# InteractionBoard_temp.net
KiCad netlist of a schematic drawn in EAGLE
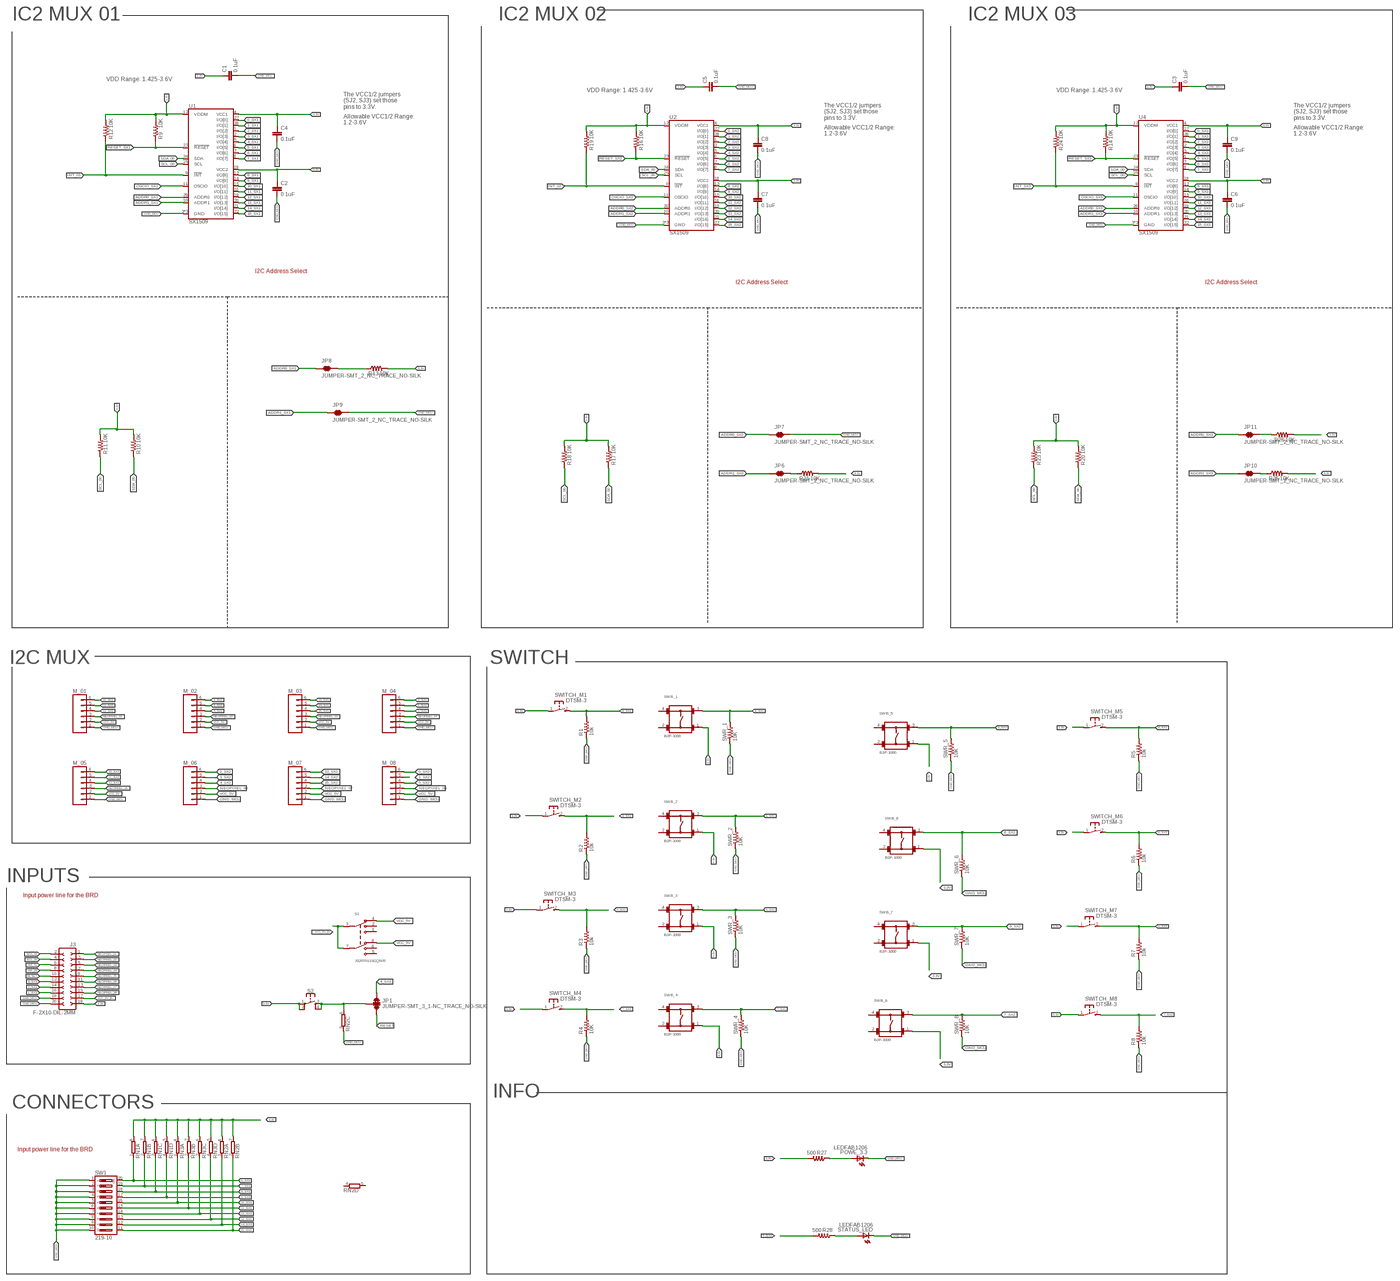
[diagram p0: schematic, sheet 1, overview]
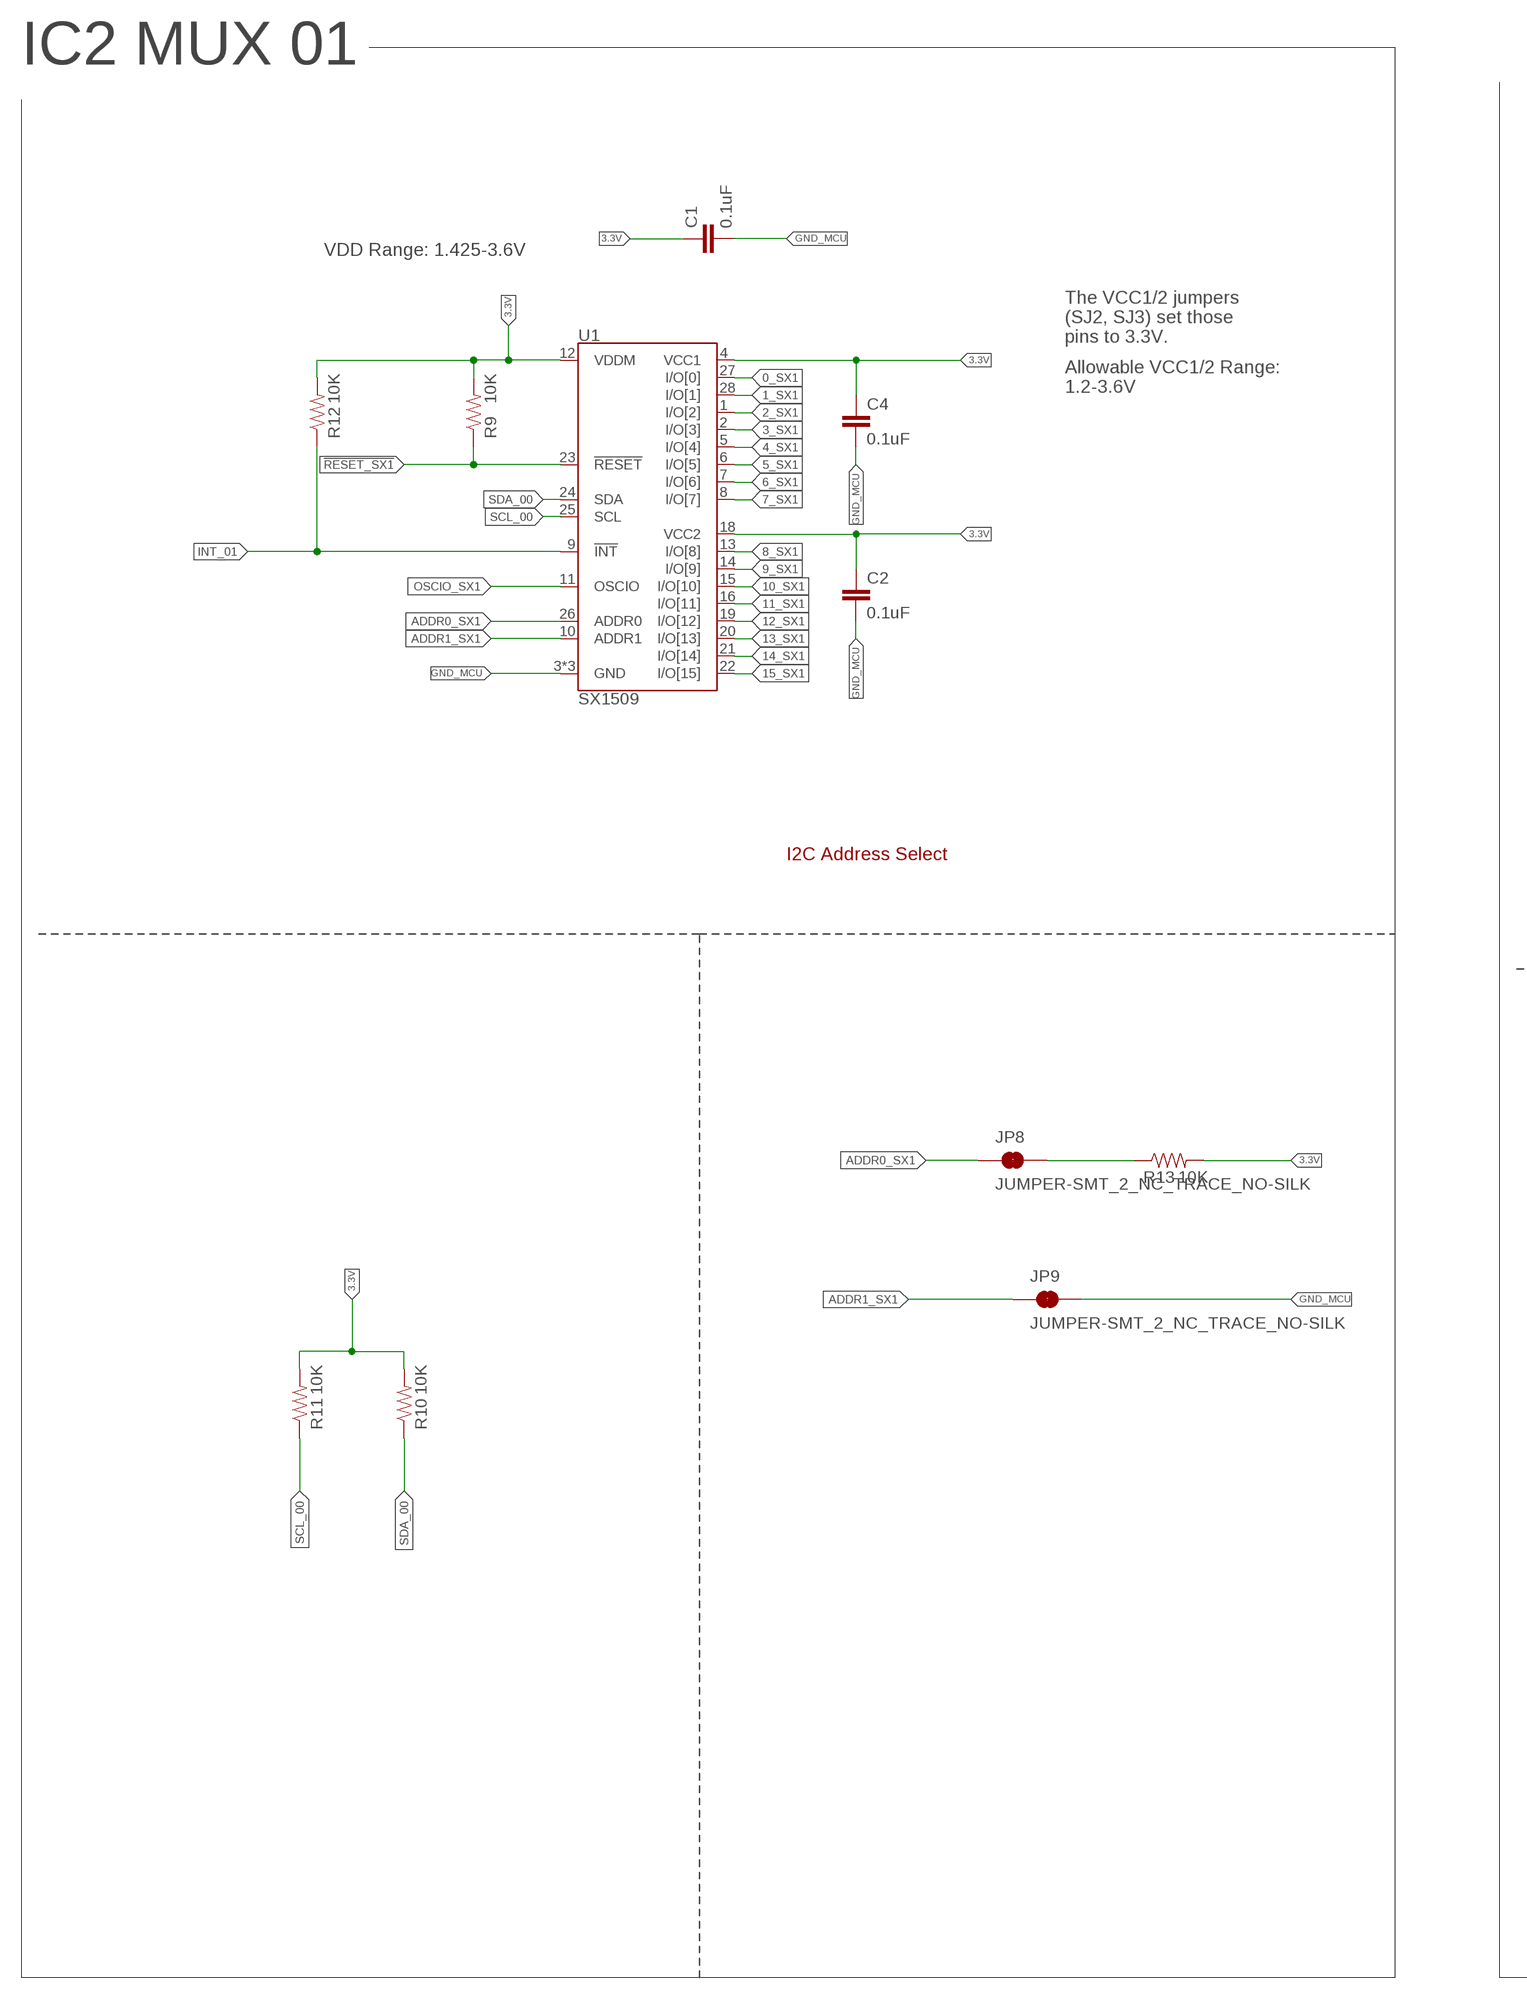
[diagram p1: schematic, sheet 1, part 1 of 4]
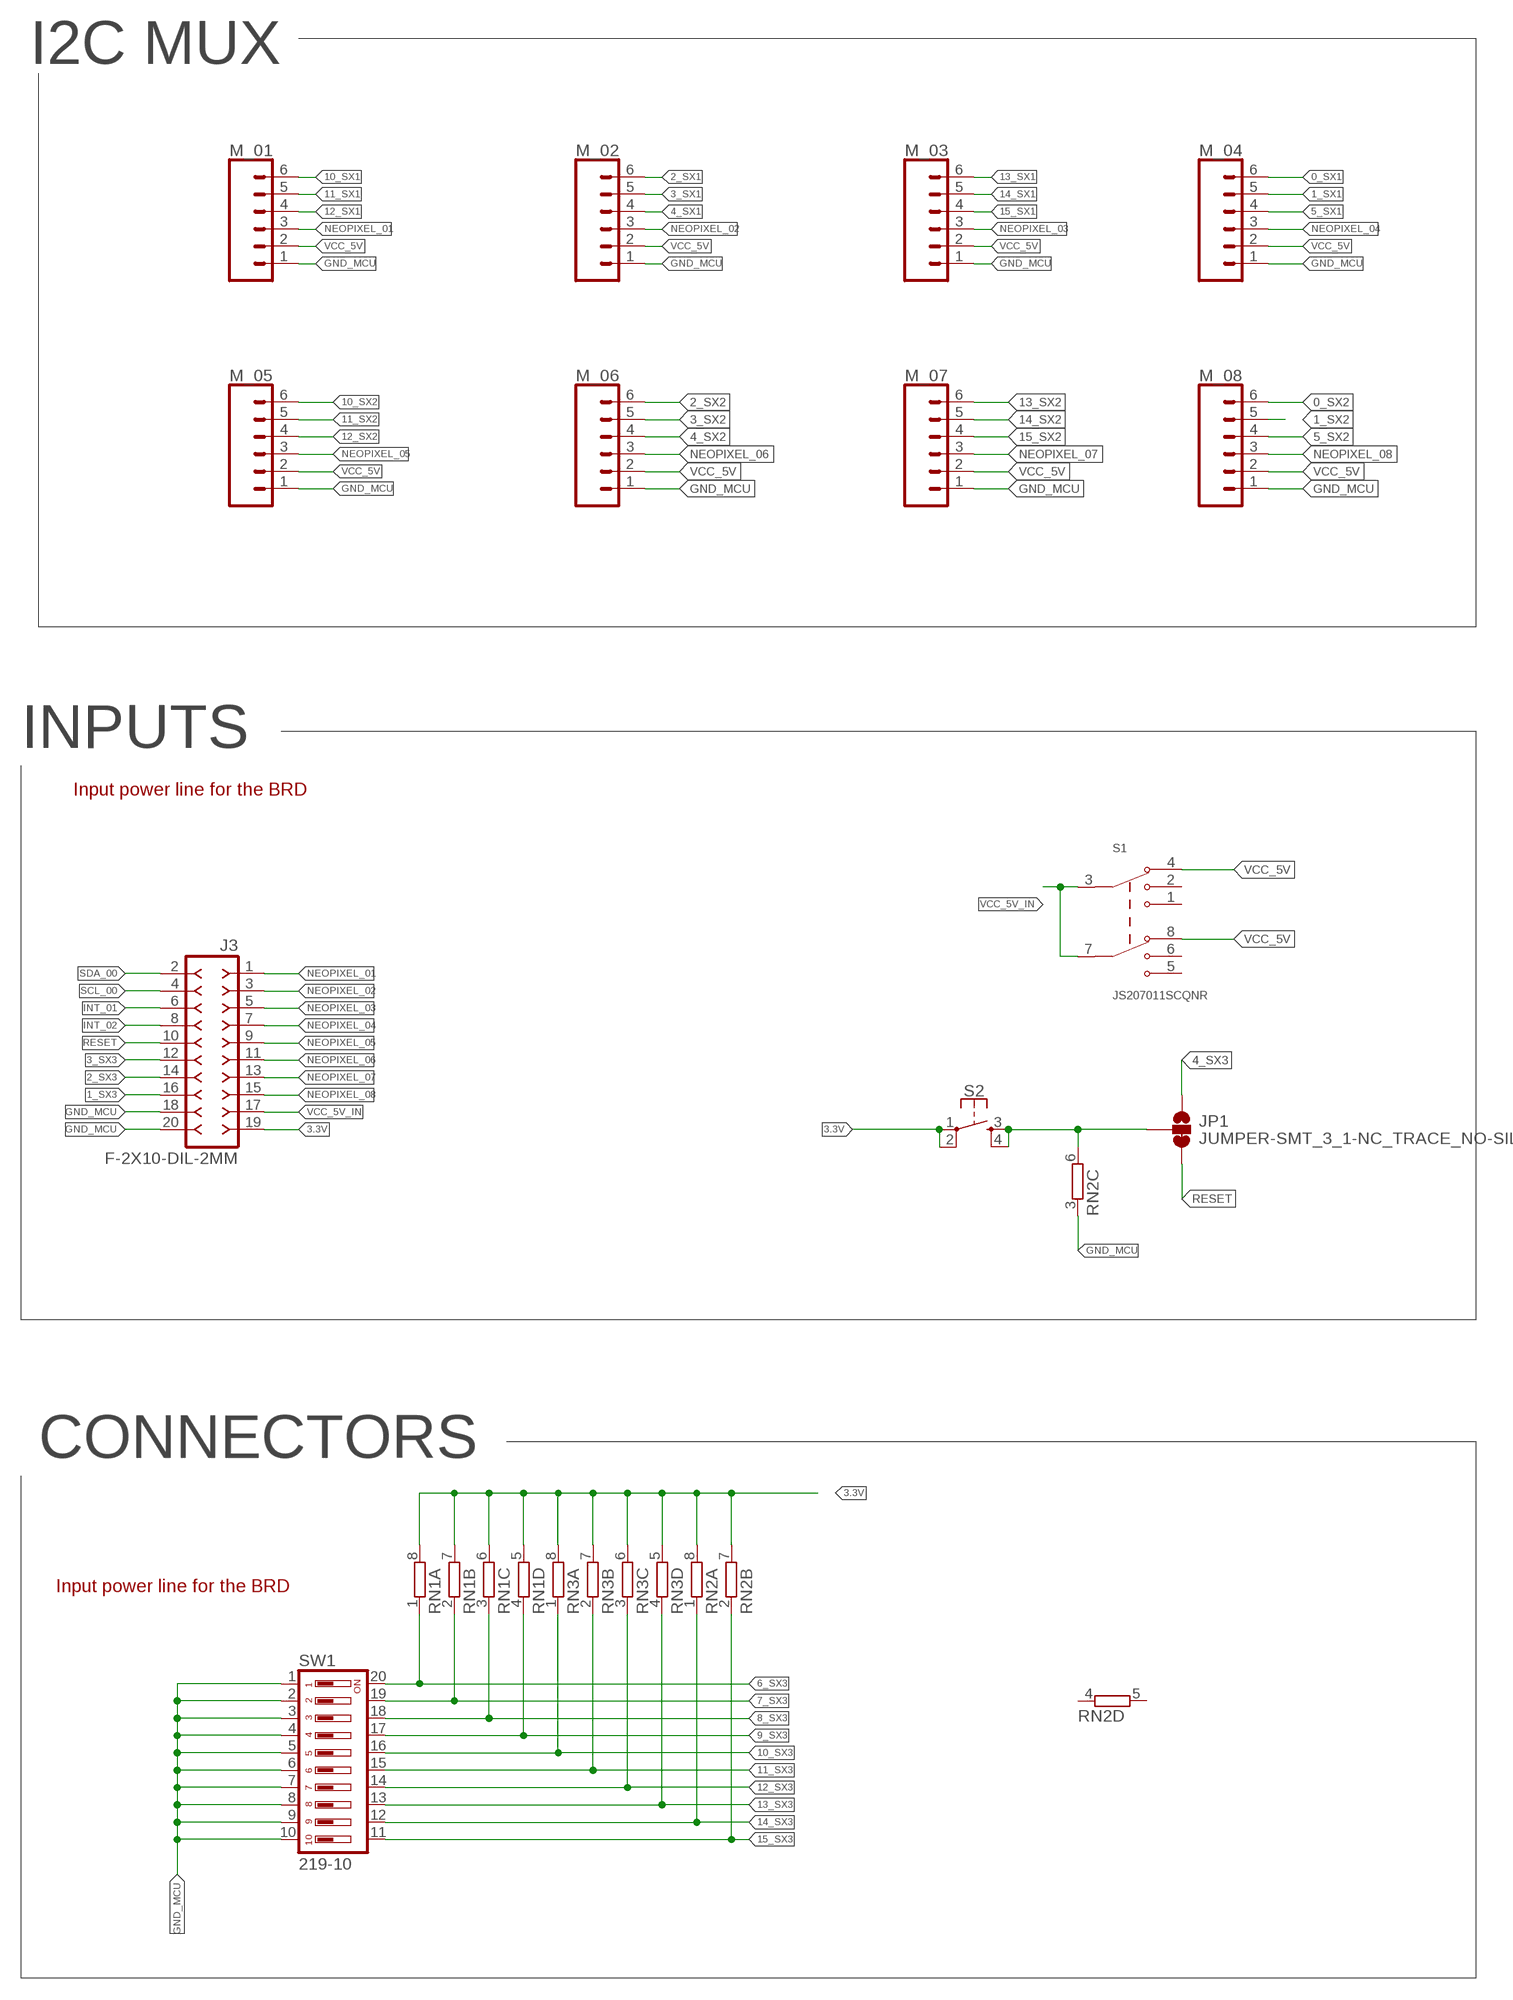
[diagram p2: schematic, sheet 1, part 2 of 4]
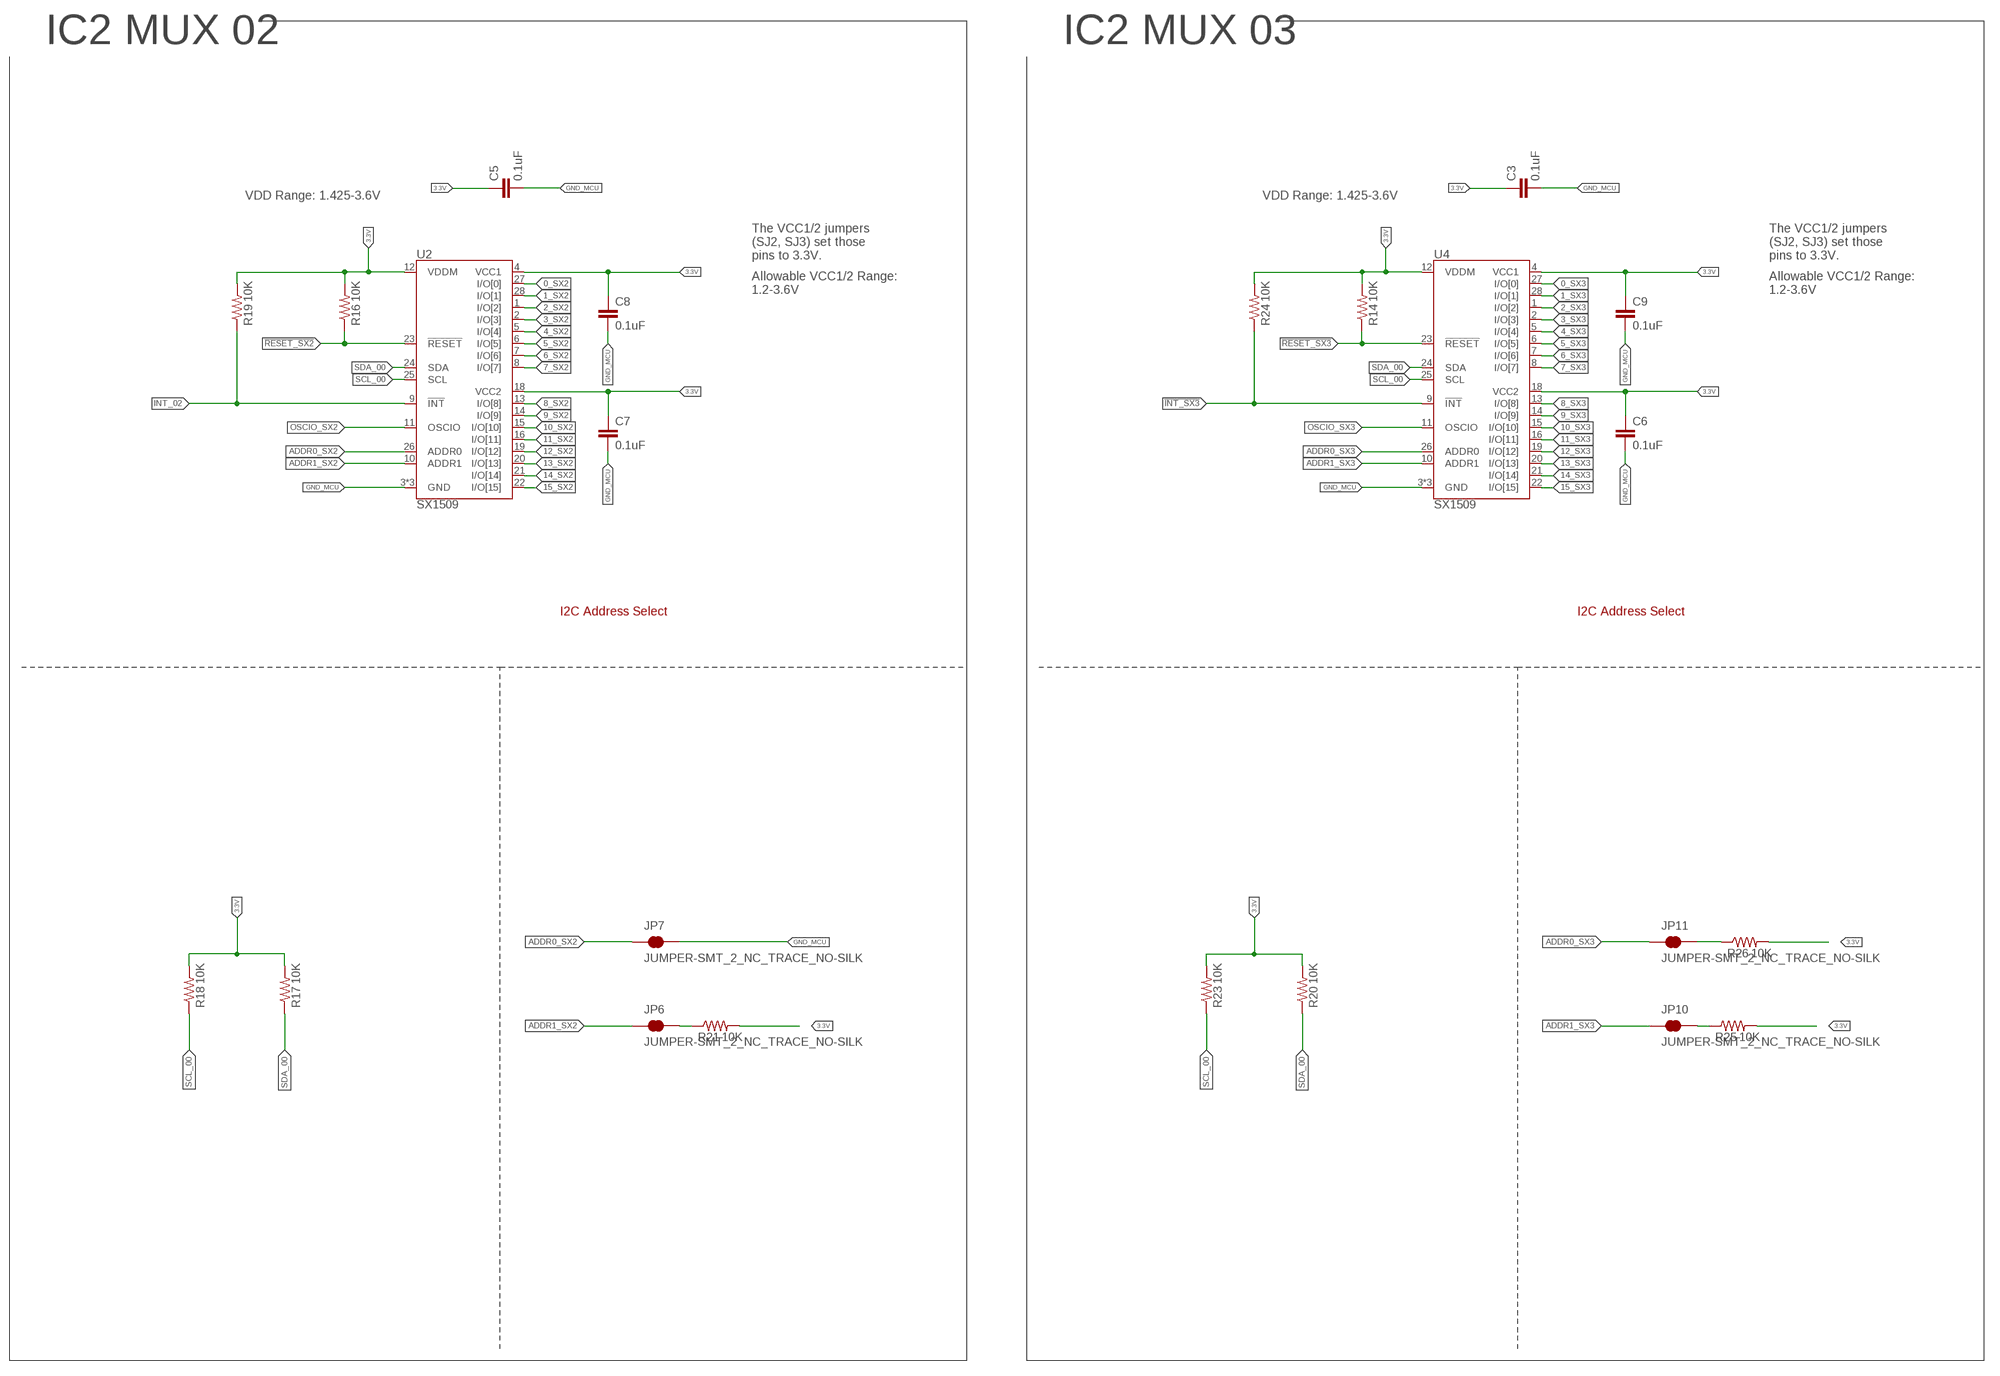
[diagram p3: schematic, sheet 1, part 3 of 4]
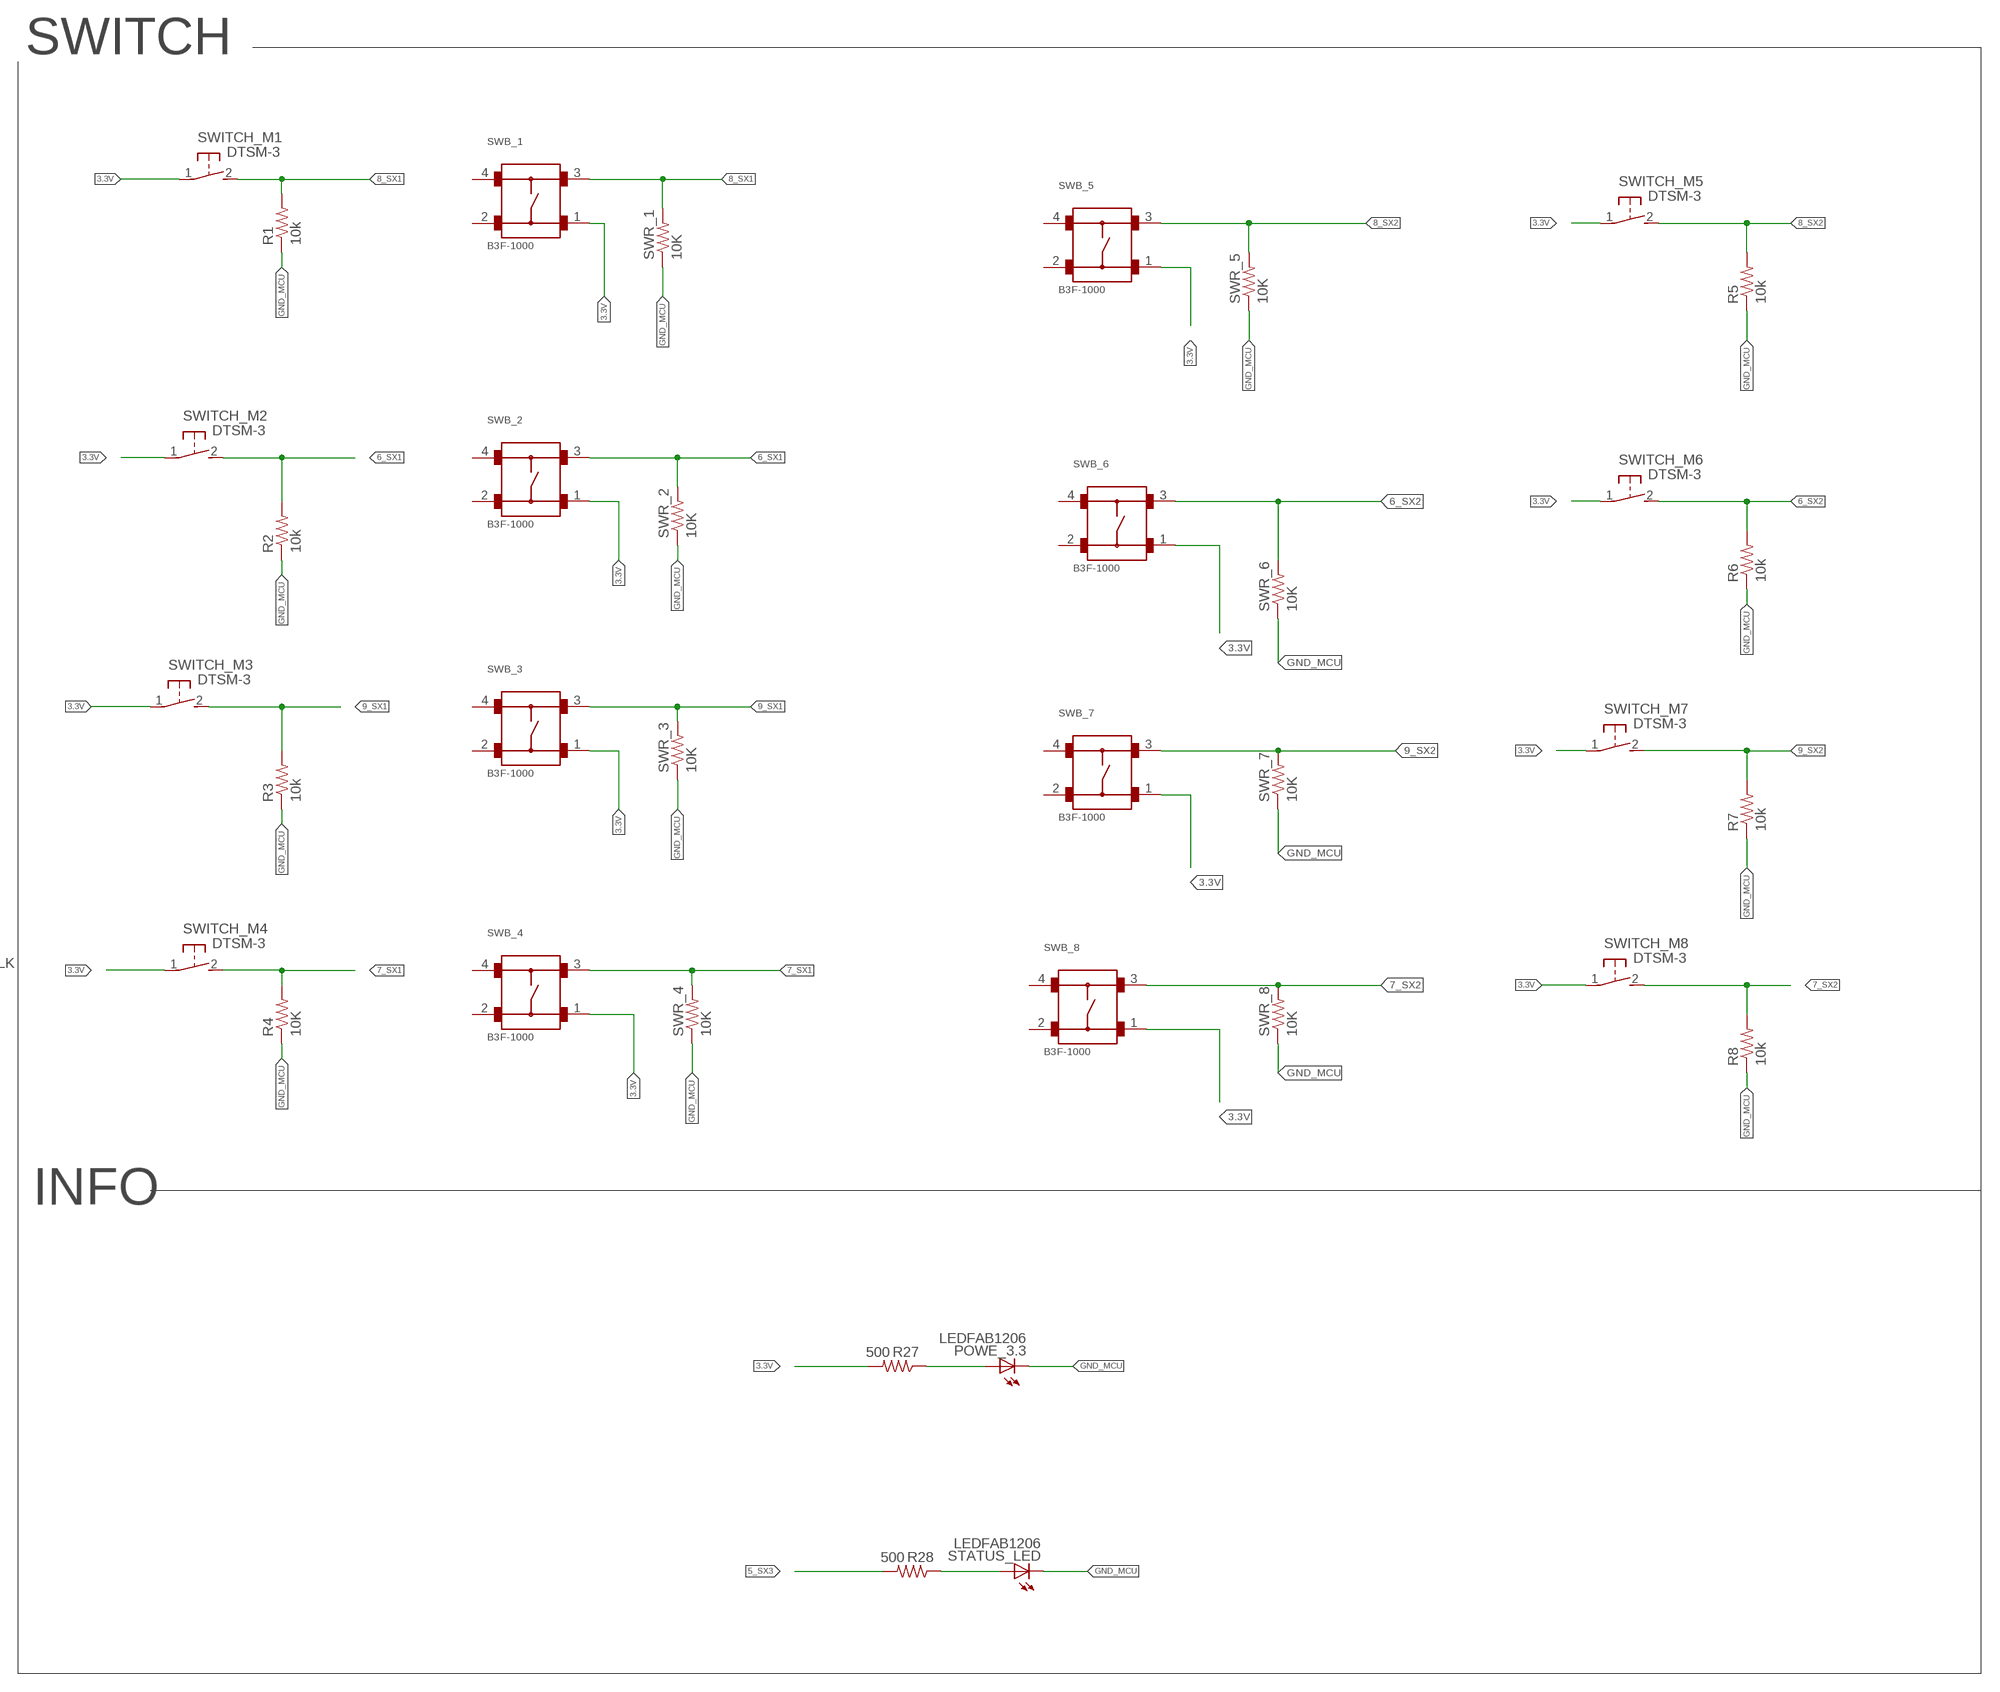
[diagram p4: schematic, sheet 1, part 4 of 4]

(export (version "E")
  (design (tool "Eeschema 10.0.6"))
  (components
    (comp (ref "C1")
      (value "0.1uF")
      (footprint "eagle-import:0603-CAP")
      (libsource (lib "eagle-import") (part "0.1UF-25V(+80/-20%)(0603)"))
    )
    (comp (ref "C2")
      (value "0.1uF")
      (footprint "eagle-import:0603-CAP")
      (libsource (lib "eagle-import") (part "0.1UF-25V(+80/-20%)(0603)"))
    )
    (comp (ref "C3")
      (value "0.1uF")
      (footprint "eagle-import:0603-CAP")
      (libsource (lib "eagle-import") (part "0.1UF-25V(+80/-20%)(0603)"))
    )
    (comp (ref "C4")
      (value "0.1uF")
      (footprint "eagle-import:0603-CAP")
      (libsource (lib "eagle-import") (part "0.1UF-25V(+80/-20%)(0603)"))
    )
    (comp (ref "C5")
      (value "0.1uF")
      (footprint "eagle-import:0603-CAP")
      (libsource (lib "eagle-import") (part "0.1UF-25V(+80/-20%)(0603)"))
    )
    (comp (ref "C6")
      (value "0.1uF")
      (footprint "eagle-import:0603-CAP")
      (libsource (lib "eagle-import") (part "0.1UF-25V(+80/-20%)(0603)"))
    )
    (comp (ref "C7")
      (value "0.1uF")
      (footprint "eagle-import:0603-CAP")
      (libsource (lib "eagle-import") (part "0.1UF-25V(+80/-20%)(0603)"))
    )
    (comp (ref "C8")
      (value "0.1uF")
      (footprint "eagle-import:0603-CAP")
      (libsource (lib "eagle-import") (part "0.1UF-25V(+80/-20%)(0603)"))
    )
    (comp (ref "C9")
      (value "0.1uF")
      (footprint "eagle-import:0603-CAP")
      (libsource (lib "eagle-import") (part "0.1UF-25V(+80/-20%)(0603)"))
    )
    (comp (ref "J3")
      (value "F-2X10-DIL-2MM")
      (footprint "eagle-import:DIL-2MM-2X10")
      (libsource (lib "eagle-import") (part "F-2X10-DIL-2MM"))
    )
    (comp (ref "JP1")
      (value "JUMPER-SMT_3_1-NC_TRACE_NO-SILK")
      (footprint "eagle-import:SMT-JUMPER_3_1-NC_TRACE_NO-SILK")
      (libsource (lib "eagle-import") (part "JUMPER-SMT_3_1-NC_TRACE_NO-SILK"))
    )
    (comp (ref "JP6")
      (value "JUMPER-SMT_2_NC_TRACE_NO-SILK")
      (footprint "eagle-import:SMT-JUMPER_2_NC_TRACE_NO-SILK")
      (libsource (lib "eagle-import") (part "JUMPER-SMT_2_NC_TRACE_NO-SILK"))
    )
    (comp (ref "JP7")
      (value "JUMPER-SMT_2_NC_TRACE_NO-SILK")
      (footprint "eagle-import:SMT-JUMPER_2_NC_TRACE_NO-SILK")
      (libsource (lib "eagle-import") (part "JUMPER-SMT_2_NC_TRACE_NO-SILK"))
    )
    (comp (ref "JP8")
      (value "JUMPER-SMT_2_NC_TRACE_NO-SILK")
      (footprint "eagle-import:SMT-JUMPER_2_NC_TRACE_NO-SILK")
      (libsource (lib "eagle-import") (part "JUMPER-SMT_2_NC_TRACE_NO-SILK"))
    )
    (comp (ref "JP9")
      (value "JUMPER-SMT_2_NC_TRACE_NO-SILK")
      (footprint "eagle-import:SMT-JUMPER_2_NC_TRACE_NO-SILK")
      (libsource (lib "eagle-import") (part "JUMPER-SMT_2_NC_TRACE_NO-SILK"))
    )
    (comp (ref "JP10")
      (value "JUMPER-SMT_2_NC_TRACE_NO-SILK")
      (footprint "eagle-import:SMT-JUMPER_2_NC_TRACE_NO-SILK")
      (libsource (lib "eagle-import") (part "JUMPER-SMT_2_NC_TRACE_NO-SILK"))
    )
    (comp (ref "JP11")
      (value "JUMPER-SMT_2_NC_TRACE_NO-SILK")
      (footprint "eagle-import:SMT-JUMPER_2_NC_TRACE_NO-SILK")
      (libsource (lib "eagle-import") (part "JUMPER-SMT_2_NC_TRACE_NO-SILK"))
    )
    (comp (ref "M_01")
      (value "CONN_06SMD-1MM")
      (footprint "eagle-import:1X06-1MM")
      (libsource (lib "eagle-import") (part "CONN_06SMD-1MM"))
    )
    (comp (ref "M_02")
      (value "CONN_06SMD-1MM")
      (footprint "eagle-import:1X06-1MM")
      (libsource (lib "eagle-import") (part "CONN_06SMD-1MM"))
    )
    (comp (ref "M_03")
      (value "CONN_06SMD-1MM")
      (footprint "eagle-import:1X06-1MM")
      (libsource (lib "eagle-import") (part "CONN_06SMD-1MM"))
    )
    (comp (ref "M_04")
      (value "CONN_06SMD-1MM")
      (footprint "eagle-import:1X06-1MM")
      (libsource (lib "eagle-import") (part "CONN_06SMD-1MM"))
    )
    (comp (ref "M_05")
      (value "CONN_06SMD-1MM")
      (footprint "eagle-import:1X06-1MM")
      (libsource (lib "eagle-import") (part "CONN_06SMD-1MM"))
    )
    (comp (ref "M_06")
      (value "CONN_06SMD-1MM")
      (footprint "eagle-import:1X06-1MM")
      (libsource (lib "eagle-import") (part "CONN_06SMD-1MM"))
    )
    (comp (ref "M_07")
      (value "CONN_06SMD-1MM")
      (footprint "eagle-import:1X06-1MM")
      (libsource (lib "eagle-import") (part "CONN_06SMD-1MM"))
    )
    (comp (ref "M_08")
      (value "CONN_06SMD-1MM")
      (footprint "eagle-import:1X06-1MM")
      (libsource (lib "eagle-import") (part "CONN_06SMD-1MM"))
    )
    (comp (ref "POWE_3.3")
      (value "LEDFAB1206")
      (footprint "eagle-import:LED1206FAB")
      (libsource (lib "eagle-import") (part "LEDFAB1206"))
    )
    (comp (ref "R1")
      (value "10k")
      (footprint "eagle-import:M0805")
      (libsource (lib "eagle-import") (part "R-US_M0805"))
    )
    (comp (ref "R2")
      (value "10k")
      (footprint "eagle-import:M0805")
      (libsource (lib "eagle-import") (part "R-US_M0805"))
    )
    (comp (ref "R3")
      (value "10k")
      (footprint "eagle-import:M0805")
      (libsource (lib "eagle-import") (part "R-US_M0805"))
    )
    (comp (ref "R4")
      (value "10K")
      (footprint "eagle-import:M0805")
      (libsource (lib "eagle-import") (part "R-US_M0805"))
    )
    (comp (ref "R5")
      (value "10k")
      (footprint "eagle-import:M0805")
      (libsource (lib "eagle-import") (part "R-US_M0805"))
    )
    (comp (ref "R6")
      (value "10k")
      (footprint "eagle-import:M0805")
      (libsource (lib "eagle-import") (part "R-US_M0805"))
    )
    (comp (ref "R7")
      (value "10k")
      (footprint "eagle-import:M0805")
      (libsource (lib "eagle-import") (part "R-US_M0805"))
    )
    (comp (ref "R8")
      (value "10k")
      (footprint "eagle-import:M0805")
      (libsource (lib "eagle-import") (part "R-US_M0805"))
    )
    (comp (ref "R9")
      (value "10K")
      (footprint "eagle-import:0603-RES")
      (libsource (lib "eagle-import") (part "SparkFun-Resistors_532_10KOHM-1/10W-1%(0603)0603"))
    )
    (comp (ref "R10")
      (value "10K")
      (footprint "eagle-import:0603-RES")
      (libsource (lib "eagle-import") (part "SparkFun-Resistors_532_10KOHM-1/10W-1%(0603)0603"))
    )
    (comp (ref "R11")
      (value "10K")
      (footprint "eagle-import:0603-RES")
      (libsource (lib "eagle-import") (part "SparkFun-Resistors_532_10KOHM-1/10W-1%(0603)0603"))
    )
    (comp (ref "R12")
      (value "10K")
      (footprint "eagle-import:0603-RES")
      (libsource (lib "eagle-import") (part "SparkFun-Resistors_532_10KOHM-1/10W-1%(0603)0603"))
    )
    (comp (ref "R13")
      (value "10K")
      (footprint "eagle-import:0603-RES")
      (libsource (lib "eagle-import") (part "SparkFun-Resistors_532_10KOHM-1/10W-1%(0603)0603"))
    )
    (comp (ref "R14")
      (value "10K")
      (footprint "eagle-import:0603-RES")
      (libsource (lib "eagle-import") (part "SparkFun-Resistors_532_10KOHM-1/10W-1%(0603)0603"))
    )
    (comp (ref "R16")
      (value "10K")
      (footprint "eagle-import:0603-RES")
      (libsource (lib "eagle-import") (part "SparkFun-Resistors_532_10KOHM-1/10W-1%(0603)0603"))
    )
    (comp (ref "R17")
      (value "10K")
      (footprint "eagle-import:0603-RES")
      (libsource (lib "eagle-import") (part "SparkFun-Resistors_532_10KOHM-1/10W-1%(0603)0603"))
    )
    (comp (ref "R18")
      (value "10K")
      (footprint "eagle-import:0603-RES")
      (libsource (lib "eagle-import") (part "SparkFun-Resistors_532_10KOHM-1/10W-1%(0603)0603"))
    )
    (comp (ref "R19")
      (value "10K")
      (footprint "eagle-import:0603-RES")
      (libsource (lib "eagle-import") (part "SparkFun-Resistors_532_10KOHM-1/10W-1%(0603)0603"))
    )
    (comp (ref "R20")
      (value "10K")
      (footprint "eagle-import:0603-RES")
      (libsource (lib "eagle-import") (part "SparkFun-Resistors_532_10KOHM-1/10W-1%(0603)0603"))
    )
    (comp (ref "R21")
      (value "10K")
      (footprint "eagle-import:0603-RES")
      (libsource (lib "eagle-import") (part "SparkFun-Resistors_532_10KOHM-1/10W-1%(0603)0603"))
    )
    (comp (ref "R23")
      (value "10K")
      (footprint "eagle-import:0603-RES")
      (libsource (lib "eagle-import") (part "SparkFun-Resistors_532_10KOHM-1/10W-1%(0603)0603"))
    )
    (comp (ref "R24")
      (value "10K")
      (footprint "eagle-import:0603-RES")
      (libsource (lib "eagle-import") (part "SparkFun-Resistors_532_10KOHM-1/10W-1%(0603)0603"))
    )
    (comp (ref "R25")
      (value "10K")
      (footprint "eagle-import:0603-RES")
      (libsource (lib "eagle-import") (part "SparkFun-Resistors_532_10KOHM-1/10W-1%(0603)0603"))
    )
    (comp (ref "R26")
      (value "10K")
      (footprint "eagle-import:0603-RES")
      (libsource (lib "eagle-import") (part "SparkFun-Resistors_532_10KOHM-1/10W-1%(0603)0603"))
    )
    (comp (ref "R27")
      (value "500")
      (footprint "eagle-import:0603-RES")
      (libsource (lib "eagle-import") (part "10KOHM-1/10W-1%(0603)0603"))
    )
    (comp (ref "R28")
      (value "500")
      (footprint "eagle-import:0603-RES")
      (libsource (lib "eagle-import") (part "10KOHM-1/10W-1%(0603)0603"))
    )
    (comp (ref "RN1")
      (value "4R-NEXB38V")
      (footprint "eagle-import:EXB38V")
      (libsource (lib "eagle-import") (part "4R-NEXB38V"))
    )
    (comp (ref "RN2")
      (value "4R-NEXB38V")
      (footprint "eagle-import:EXB38V")
      (libsource (lib "eagle-import") (part "4R-NEXB38V"))
    )
    (comp (ref "RN3")
      (value "4R-NEXB38V")
      (footprint "eagle-import:EXB38V")
      (libsource (lib "eagle-import") (part "4R-NEXB38V"))
    )
    (comp (ref "S1")
      (value "JS207011SCQNR")
      (footprint "eagle-import:SW_JS207011SCQNR")
      (fields (field (name "MF") "C&K"))
      (libsource (lib "eagle-import") (part "JS207011SCQNR"))
    )
    (comp (ref "S2")
      (value "MOMENTARY-SWITCH-SPST-2-SMD-5.2MM")
      (footprint "eagle-import:TACTILE_SWITCH_SMD_5.2MM")
      (libsource (lib "eagle-import") (part "MOMENTARY-SWITCH-SPST-2-SMD-5.2MM"))
    )
    (comp (ref "STATUS_LED")
      (value "LEDFAB1206")
      (footprint "eagle-import:LED1206FAB")
      (libsource (lib "eagle-import") (part "LEDFAB1206"))
    )
    (comp (ref "SW1")
      (value "219-10")
      (footprint "eagle-import:CTS-219-10")
      (fields (field (name "MF") "SLI (CML/IDI)") (field (name "MPN") "219-10PK"))
      (libsource (lib "eagle-import") (part "219-10"))
    )
    (comp (ref "SWB_1")
      (value "B3F-1000")
      (footprint "eagle-import:B3F-1000")
      (fields
        (field (name "DIGI_KEY_PART_NUMBER") "SW400-ND")
        (field (name "MANUFACTURER") "Omron Electronics Inc-EMC Div")
        (field (name "CREATED_BY") "PCBLayout.com")
      )
      (libsource (lib "eagle-import") (part "B3F-1000"))
    )
    (comp (ref "SWB_2")
      (value "B3F-1000")
      (footprint "eagle-import:B3F-1000")
      (fields
        (field (name "DIGI_KEY_PART_NUMBER") "SW400-ND")
        (field (name "MANUFACTURER") "Omron Electronics Inc-EMC Div")
        (field (name "CREATED_BY") "PCBLayout.com")
      )
      (libsource (lib "eagle-import") (part "B3F-1000"))
    )
    (comp (ref "SWB_3")
      (value "B3F-1000")
      (footprint "eagle-import:B3F-1000")
      (fields
        (field (name "DIGI_KEY_PART_NUMBER") "SW400-ND")
        (field (name "MANUFACTURER") "Omron Electronics Inc-EMC Div")
        (field (name "CREATED_BY") "PCBLayout.com")
      )
      (libsource (lib "eagle-import") (part "B3F-1000"))
    )
    (comp (ref "SWB_4")
      (value "B3F-1000")
      (footprint "eagle-import:B3F-1000")
      (fields
        (field (name "DIGI_KEY_PART_NUMBER") "SW400-ND")
        (field (name "MANUFACTURER") "Omron Electronics Inc-EMC Div")
        (field (name "CREATED_BY") "PCBLayout.com")
      )
      (libsource (lib "eagle-import") (part "B3F-1000"))
    )
    (comp (ref "SWB_5")
      (value "B3F-1000")
      (footprint "eagle-import:B3F-1000")
      (fields
        (field (name "DIGI_KEY_PART_NUMBER") "SW400-ND")
        (field (name "MANUFACTURER") "Omron Electronics Inc-EMC Div")
        (field (name "CREATED_BY") "PCBLayout.com")
      )
      (libsource (lib "eagle-import") (part "B3F-1000"))
    )
    (comp (ref "SWB_6")
      (value "B3F-1000")
      (footprint "eagle-import:B3F-1000")
      (fields
        (field (name "DIGI_KEY_PART_NUMBER") "SW400-ND")
        (field (name "MANUFACTURER") "Omron Electronics Inc-EMC Div")
        (field (name "CREATED_BY") "PCBLayout.com")
      )
      (libsource (lib "eagle-import") (part "B3F-1000"))
    )
    (comp (ref "SWB_7")
      (value "B3F-1000")
      (footprint "eagle-import:B3F-1000")
      (fields
        (field (name "DIGI_KEY_PART_NUMBER") "SW400-ND")
        (field (name "MANUFACTURER") "Omron Electronics Inc-EMC Div")
        (field (name "CREATED_BY") "PCBLayout.com")
      )
      (libsource (lib "eagle-import") (part "B3F-1000"))
    )
    (comp (ref "SWB_8")
      (value "B3F-1000")
      (footprint "eagle-import:B3F-1000")
      (fields
        (field (name "DIGI_KEY_PART_NUMBER") "SW400-ND")
        (field (name "MANUFACTURER") "Omron Electronics Inc-EMC Div")
        (field (name "CREATED_BY") "PCBLayout.com")
      )
      (libsource (lib "eagle-import") (part "B3F-1000"))
    )
    (comp (ref "SWITCH_M1")
      (value "DTSM-3")
      (footprint "eagle-import:DTSM-3")
      (libsource (lib "eagle-import") (part "DTSM-3"))
    )
    (comp (ref "SWITCH_M2")
      (value "DTSM-3")
      (footprint "eagle-import:DTSM-3")
      (libsource (lib "eagle-import") (part "DTSM-3"))
    )
    (comp (ref "SWITCH_M3")
      (value "DTSM-3")
      (footprint "eagle-import:DTSM-3")
      (libsource (lib "eagle-import") (part "DTSM-3"))
    )
    (comp (ref "SWITCH_M4")
      (value "DTSM-3")
      (footprint "eagle-import:DTSM-3")
      (libsource (lib "eagle-import") (part "DTSM-3"))
    )
    (comp (ref "SWITCH_M5")
      (value "DTSM-3")
      (footprint "eagle-import:DTSM-3")
      (libsource (lib "eagle-import") (part "DTSM-3"))
    )
    (comp (ref "SWITCH_M6")
      (value "DTSM-3")
      (footprint "eagle-import:DTSM-3")
      (libsource (lib "eagle-import") (part "DTSM-3"))
    )
    (comp (ref "SWITCH_M7")
      (value "DTSM-3")
      (footprint "eagle-import:DTSM-3")
      (libsource (lib "eagle-import") (part "DTSM-3"))
    )
    (comp (ref "SWITCH_M8")
      (value "DTSM-3")
      (footprint "eagle-import:DTSM-3")
      (libsource (lib "eagle-import") (part "DTSM-3"))
    )
    (comp (ref "SWR_1")
      (value "10K")
      (footprint "eagle-import:M0805")
      (libsource (lib "eagle-import") (part "R-US_M0805"))
    )
    (comp (ref "SWR_2")
      (value "10K")
      (footprint "eagle-import:M0805")
      (libsource (lib "eagle-import") (part "R-US_M0805"))
    )
    (comp (ref "SWR_3")
      (value "10K")
      (footprint "eagle-import:M0805")
      (libsource (lib "eagle-import") (part "R-US_M0805"))
    )
    (comp (ref "SWR_4")
      (value "10K")
      (footprint "eagle-import:M0805")
      (libsource (lib "eagle-import") (part "R-US_M0805"))
    )
    (comp (ref "SWR_5")
      (value "10K")
      (footprint "eagle-import:M0805")
      (libsource (lib "eagle-import") (part "R-US_M0805"))
    )
    (comp (ref "SWR_6")
      (value "10K")
      (footprint "eagle-import:M0805")
      (libsource (lib "eagle-import") (part "R-US_M0805"))
    )
    (comp (ref "SWR_7")
      (value "10K")
      (footprint "eagle-import:M0805")
      (libsource (lib "eagle-import") (part "R-US_M0805"))
    )
    (comp (ref "SWR_8")
      (value "10K")
      (footprint "eagle-import:M0805")
      (libsource (lib "eagle-import") (part "R-US_M0805"))
    )
    (comp (ref "U1")
      (value "SX1509")
      (footprint "eagle-import:QFN-28")
      (libsource (lib "eagle-import") (part "SX1509"))
    )
    (comp (ref "U2")
      (value "SX1509")
      (footprint "eagle-import:QFN-28")
      (libsource (lib "eagle-import") (part "SX1509"))
    )
    (comp (ref "U4")
      (value "SX1509")
      (footprint "eagle-import:QFN-28")
      (libsource (lib "eagle-import") (part "SX1509"))
    )
  )
  (nets
    (net (code "1") (name "/~{INT_SX3}") (class "Default")
      (node (ref "R24") (pin "1") (pinfunction "1_1") (pintype "passive"))
      (node (ref "U4") (pin "9") (pinfunction "~{INT}_9") (pintype "bidirectional"))
    )
    (net (code "2") (name "/~{RESET_SX1}") (class "Default")
      (node (ref "R9") (pin "1") (pinfunction "1_1") (pintype "passive"))
      (node (ref "U1") (pin "23") (pinfunction "~{RESET}_23") (pintype "bidirectional"))
    )
    (net (code "3") (name "/~{RESET_SX2}") (class "Default")
      (node (ref "R16") (pin "1") (pinfunction "1_1") (pintype "passive"))
      (node (ref "U2") (pin "23") (pinfunction "~{RESET}_23") (pintype "bidirectional"))
    )
    (net (code "4") (name "/~{RESET_SX3}") (class "Default")
      (node (ref "R14") (pin "1") (pinfunction "1_1") (pintype "passive"))
      (node (ref "U4") (pin "23") (pinfunction "~{RESET}_23") (pintype "bidirectional"))
    )
    (net (code "5") (name "0_SX1") (class "Default")
      (node (ref "M_04") (pin "6") (pinfunction "6_6") (pintype "passive"))
      (node (ref "U1") (pin "27") (pinfunction "I/O[0]_27") (pintype "bidirectional"))
    )
    (net (code "6") (name "0_SX2") (class "Default")
      (node (ref "M_08") (pin "6") (pinfunction "6_6") (pintype "passive"))
      (node (ref "U2") (pin "27") (pinfunction "I/O[0]_27") (pintype "bidirectional"))
    )
    (net (code "7") (name "0_SX3") (class "Default")
      (node (ref "U4") (pin "27") (pinfunction "I/O[0]_27") (pintype "bidirectional"))
    )
    (net (code "8") (name "1_SX1") (class "Default")
      (node (ref "M_04") (pin "5") (pinfunction "5_5") (pintype "passive"))
      (node (ref "U1") (pin "28") (pinfunction "I/O[1]_28") (pintype "bidirectional"))
    )
    (net (code "9") (name "1_SX2") (class "Default")
      (node (ref "M_08") (pin "5") (pinfunction "5_5") (pintype "passive"))
      (node (ref "U2") (pin "28") (pinfunction "I/O[1]_28") (pintype "bidirectional"))
    )
    (net (code "10") (name "1_SX3") (class "Default")
      (node (ref "J3") (pin "16") (pinfunction "16_16") (pintype "passive"))
      (node (ref "U4") (pin "28") (pinfunction "I/O[1]_28") (pintype "bidirectional"))
    )
    (net (code "11") (name "2_SX1") (class "Default")
      (node (ref "M_02") (pin "6") (pinfunction "6_6") (pintype "passive"))
      (node (ref "U1") (pin "1") (pinfunction "I/O[2]_1") (pintype "bidirectional"))
    )
    (net (code "12") (name "2_SX2") (class "Default")
      (node (ref "M_06") (pin "6") (pinfunction "6_6") (pintype "passive"))
      (node (ref "U2") (pin "1") (pinfunction "I/O[2]_1") (pintype "bidirectional"))
    )
    (net (code "13") (name "2_SX3") (class "Default")
      (node (ref "J3") (pin "14") (pinfunction "14_14") (pintype "passive"))
      (node (ref "U4") (pin "1") (pinfunction "I/O[2]_1") (pintype "bidirectional"))
    )
    (net (code "14") (name "3.3V") (class "Default")
      (node (ref "C1") (pin "1") (pinfunction "1_1") (pintype "passive"))
      (node (ref "C2") (pin "1") (pinfunction "1_1") (pintype "passive"))
      (node (ref "C3") (pin "1") (pinfunction "1_1") (pintype "passive"))
      (node (ref "C4") (pin "1") (pinfunction "1_1") (pintype "passive"))
      (node (ref "C5") (pin "1") (pinfunction "1_1") (pintype "passive"))
      (node (ref "C6") (pin "1") (pinfunction "1_1") (pintype "passive"))
      (node (ref "C7") (pin "1") (pinfunction "1_1") (pintype "passive"))
      (node (ref "C8") (pin "1") (pinfunction "1_1") (pintype "passive"))
      (node (ref "C9") (pin "1") (pinfunction "1_1") (pintype "passive"))
      (node (ref "J3") (pin "19") (pinfunction "19_19") (pintype "passive"))
      (node (ref "R10") (pin "2") (pinfunction "2_2") (pintype "passive"))
      (node (ref "R11") (pin "2") (pinfunction "2_2") (pintype "passive"))
      (node (ref "R12") (pin "2") (pinfunction "2_2") (pintype "passive"))
      (node (ref "R13") (pin "2") (pinfunction "2_2") (pintype "passive"))
      (node (ref "R14") (pin "2") (pinfunction "2_2") (pintype "passive"))
      (node (ref "R16") (pin "2") (pinfunction "2_2") (pintype "passive"))
      (node (ref "R17") (pin "2") (pinfunction "2_2") (pintype "passive"))
      (node (ref "R18") (pin "2") (pinfunction "2_2") (pintype "passive"))
      (node (ref "R19") (pin "2") (pinfunction "2_2") (pintype "passive"))
      (node (ref "R20") (pin "2") (pinfunction "2_2") (pintype "passive"))
      (node (ref "R21") (pin "2") (pinfunction "2_2") (pintype "passive"))
      (node (ref "R23") (pin "2") (pinfunction "2_2") (pintype "passive"))
      (node (ref "R24") (pin "2") (pinfunction "2_2") (pintype "passive"))
      (node (ref "R25") (pin "2") (pinfunction "2_2") (pintype "passive"))
      (node (ref "R26") (pin "2") (pinfunction "2_2") (pintype "passive"))
      (node (ref "R27") (pin "2") (pinfunction "2_2") (pintype "passive"))
      (node (ref "R9") (pin "2") (pinfunction "2_2") (pintype "passive"))
      (node (ref "RN1") (pin "5") (pinfunction "2_5") (pintype "passive"))
      (node (ref "RN1") (pin "6") (pinfunction "2_6") (pintype "passive"))
      (node (ref "RN1") (pin "7") (pinfunction "2_7") (pintype "passive"))
      (node (ref "RN1") (pin "8") (pinfunction "2_8") (pintype "passive"))
      (node (ref "RN2") (pin "7") (pinfunction "2_7") (pintype "passive"))
      (node (ref "RN2") (pin "8") (pinfunction "2_8") (pintype "passive"))
      (node (ref "RN3") (pin "5") (pinfunction "2_5") (pintype "passive"))
      (node (ref "RN3") (pin "6") (pinfunction "2_6") (pintype "passive"))
      (node (ref "RN3") (pin "7") (pinfunction "2_7") (pintype "passive"))
      (node (ref "RN3") (pin "8") (pinfunction "2_8") (pintype "passive"))
      (node (ref "S2") (pin "1") (pinfunction "1_1") (pintype "passive"))
      (node (ref "S2") (pin "2") (pinfunction "2_2") (pintype "passive"))
      (node (ref "SWB_1") (pin "1") (pinfunction "1_1") (pintype "passive"))
      (node (ref "SWB_2") (pin "1") (pinfunction "1_1") (pintype "passive"))
      (node (ref "SWB_3") (pin "1") (pinfunction "1_1") (pintype "passive"))
      (node (ref "SWB_4") (pin "1") (pinfunction "1_1") (pintype "passive"))
      (node (ref "SWB_5") (pin "1") (pinfunction "1_1") (pintype "passive"))
      (node (ref "SWB_6") (pin "1") (pinfunction "1_1") (pintype "passive"))
      (node (ref "SWB_7") (pin "1") (pinfunction "1_1") (pintype "passive"))
      (node (ref "SWB_8") (pin "1") (pinfunction "1_1") (pintype "passive"))
      (node (ref "SWITCH_M1") (pin "1") (pinfunction "1_1") (pintype "passive"))
      (node (ref "SWITCH_M2") (pin "1") (pinfunction "1_1") (pintype "passive"))
      (node (ref "SWITCH_M3") (pin "1") (pinfunction "1_1") (pintype "passive"))
      (node (ref "SWITCH_M4") (pin "1") (pinfunction "1_1") (pintype "passive"))
      (node (ref "SWITCH_M5") (pin "1") (pinfunction "1_1") (pintype "passive"))
      (node (ref "SWITCH_M6") (pin "1") (pinfunction "1_1") (pintype "passive"))
      (node (ref "SWITCH_M7") (pin "1") (pinfunction "1_1") (pintype "passive"))
      (node (ref "SWITCH_M8") (pin "1") (pinfunction "1_1") (pintype "passive"))
      (node (ref "U1") (pin "12") (pinfunction "VDDM_12") (pintype "bidirectional"))
      (node (ref "U1") (pin "18") (pinfunction "VCC2_18") (pintype "bidirectional"))
      (node (ref "U1") (pin "4") (pinfunction "VCC1_4") (pintype "bidirectional"))
      (node (ref "U2") (pin "12") (pinfunction "VDDM_12") (pintype "bidirectional"))
      (node (ref "U2") (pin "18") (pinfunction "VCC2_18") (pintype "bidirectional"))
      (node (ref "U2") (pin "4") (pinfunction "VCC1_4") (pintype "bidirectional"))
      (node (ref "U4") (pin "12") (pinfunction "VDDM_12") (pintype "bidirectional"))
      (node (ref "U4") (pin "18") (pinfunction "VCC2_18") (pintype "bidirectional"))
      (node (ref "U4") (pin "4") (pinfunction "VCC1_4") (pintype "bidirectional"))
    )
    (net (code "15") (name "3_SX1") (class "Default")
      (node (ref "M_02") (pin "5") (pinfunction "5_5") (pintype "passive"))
      (node (ref "U1") (pin "2") (pinfunction "I/O[3]_2") (pintype "bidirectional"))
    )
    (net (code "16") (name "3_SX2") (class "Default")
      (node (ref "M_06") (pin "5") (pinfunction "5_5") (pintype "passive"))
      (node (ref "U2") (pin "2") (pinfunction "I/O[3]_2") (pintype "bidirectional"))
    )
    (net (code "17") (name "3_SX3") (class "Default")
      (node (ref "J3") (pin "12") (pinfunction "12_12") (pintype "passive"))
      (node (ref "U4") (pin "2") (pinfunction "I/O[3]_2") (pintype "bidirectional"))
    )
    (net (code "18") (name "4_SX1") (class "Default")
      (node (ref "M_02") (pin "4") (pinfunction "4_4") (pintype "passive"))
      (node (ref "U1") (pin "5") (pinfunction "I/O[4]_5") (pintype "bidirectional"))
    )
    (net (code "19") (name "4_SX2") (class "Default")
      (node (ref "M_06") (pin "4") (pinfunction "4_4") (pintype "passive"))
      (node (ref "U2") (pin "5") (pinfunction "I/O[4]_5") (pintype "bidirectional"))
    )
    (net (code "20") (name "4_SX3") (class "Default")
      (node (ref "JP1") (pin "1") (pinfunction "1_1") (pintype "passive"))
      (node (ref "U4") (pin "5") (pinfunction "I/O[4]_5") (pintype "bidirectional"))
    )
    (net (code "21") (name "5_SX1") (class "Default")
      (node (ref "M_04") (pin "4") (pinfunction "4_4") (pintype "passive"))
      (node (ref "U1") (pin "6") (pinfunction "I/O[5]_6") (pintype "bidirectional"))
    )
    (net (code "22") (name "5_SX2") (class "Default")
      (node (ref "M_08") (pin "4") (pinfunction "4_4") (pintype "passive"))
      (node (ref "U2") (pin "6") (pinfunction "I/O[5]_6") (pintype "bidirectional"))
    )
    (net (code "23") (name "5_SX3") (class "Default")
      (node (ref "R28") (pin "2") (pinfunction "2_2") (pintype "passive"))
      (node (ref "U4") (pin "6") (pinfunction "I/O[5]_6") (pintype "bidirectional"))
    )
    (net (code "24") (name "6_SX1") (class "Default")
      (node (ref "R2") (pin "2") (pinfunction "2_2") (pintype "passive"))
      (node (ref "SWB_2") (pin "3") (pinfunction "3_3") (pintype "passive"))
      (node (ref "SWITCH_M2") (pin "2") (pinfunction "2_2") (pintype "passive"))
      (node (ref "SWR_2") (pin "2") (pinfunction "2_2") (pintype "passive"))
      (node (ref "U1") (pin "7") (pinfunction "I/O[6]_7") (pintype "bidirectional"))
    )
    (net (code "25") (name "6_SX2") (class "Default")
      (node (ref "R6") (pin "2") (pinfunction "2_2") (pintype "passive"))
      (node (ref "SWB_6") (pin "3") (pinfunction "3_3") (pintype "passive"))
      (node (ref "SWITCH_M6") (pin "2") (pinfunction "2_2") (pintype "passive"))
      (node (ref "SWR_6") (pin "2") (pinfunction "2_2") (pintype "passive"))
      (node (ref "U2") (pin "7") (pinfunction "I/O[6]_7") (pintype "bidirectional"))
    )
    (net (code "26") (name "6_SX3") (class "Default")
      (node (ref "RN1") (pin "1") (pinfunction "1_1") (pintype "passive"))
      (node (ref "SW1") (pin "20") (pinfunction "20_20") (pintype "passive"))
      (node (ref "U4") (pin "7") (pinfunction "I/O[6]_7") (pintype "bidirectional"))
    )
    (net (code "27") (name "7_SX1") (class "Default")
      (node (ref "R4") (pin "2") (pinfunction "2_2") (pintype "passive"))
      (node (ref "SWB_4") (pin "3") (pinfunction "3_3") (pintype "passive"))
      (node (ref "SWITCH_M4") (pin "2") (pinfunction "2_2") (pintype "passive"))
      (node (ref "SWR_4") (pin "2") (pinfunction "2_2") (pintype "passive"))
      (node (ref "U1") (pin "8") (pinfunction "I/O[7]_8") (pintype "bidirectional"))
    )
    (net (code "28") (name "7_SX2") (class "Default")
      (node (ref "R8") (pin "2") (pinfunction "2_2") (pintype "passive"))
      (node (ref "SWB_8") (pin "3") (pinfunction "3_3") (pintype "passive"))
      (node (ref "SWITCH_M8") (pin "2") (pinfunction "2_2") (pintype "passive"))
      (node (ref "SWR_8") (pin "2") (pinfunction "2_2") (pintype "passive"))
      (node (ref "U2") (pin "8") (pinfunction "I/O[7]_8") (pintype "bidirectional"))
    )
    (net (code "29") (name "7_SX3") (class "Default")
      (node (ref "RN1") (pin "2") (pinfunction "1_2") (pintype "passive"))
      (node (ref "SW1") (pin "19") (pinfunction "19_19") (pintype "passive"))
      (node (ref "U4") (pin "8") (pinfunction "I/O[7]_8") (pintype "bidirectional"))
    )
    (net (code "30") (name "8_SX1") (class "Default")
      (node (ref "R1") (pin "2") (pinfunction "2_2") (pintype "passive"))
      (node (ref "SWB_1") (pin "3") (pinfunction "3_3") (pintype "passive"))
      (node (ref "SWITCH_M1") (pin "2") (pinfunction "2_2") (pintype "passive"))
      (node (ref "SWR_1") (pin "2") (pinfunction "2_2") (pintype "passive"))
      (node (ref "U1") (pin "13") (pinfunction "I/O[8]_13") (pintype "bidirectional"))
    )
    (net (code "31") (name "8_SX2") (class "Default")
      (node (ref "R5") (pin "2") (pinfunction "2_2") (pintype "passive"))
      (node (ref "SWB_5") (pin "3") (pinfunction "3_3") (pintype "passive"))
      (node (ref "SWITCH_M5") (pin "2") (pinfunction "2_2") (pintype "passive"))
      (node (ref "SWR_5") (pin "2") (pinfunction "2_2") (pintype "passive"))
      (node (ref "U2") (pin "13") (pinfunction "I/O[8]_13") (pintype "bidirectional"))
    )
    (net (code "32") (name "8_SX3") (class "Default")
      (node (ref "RN1") (pin "3") (pinfunction "1_3") (pintype "passive"))
      (node (ref "SW1") (pin "18") (pinfunction "18_18") (pintype "passive"))
      (node (ref "U4") (pin "13") (pinfunction "I/O[8]_13") (pintype "bidirectional"))
    )
    (net (code "33") (name "9_SX1") (class "Default")
      (node (ref "R3") (pin "2") (pinfunction "2_2") (pintype "passive"))
      (node (ref "SWB_3") (pin "3") (pinfunction "3_3") (pintype "passive"))
      (node (ref "SWITCH_M3") (pin "2") (pinfunction "2_2") (pintype "passive"))
      (node (ref "SWR_3") (pin "2") (pinfunction "2_2") (pintype "passive"))
      (node (ref "U1") (pin "14") (pinfunction "I/O[9]_14") (pintype "bidirectional"))
    )
    (net (code "34") (name "9_SX2") (class "Default")
      (node (ref "R7") (pin "2") (pinfunction "2_2") (pintype "passive"))
      (node (ref "SWB_7") (pin "3") (pinfunction "3_3") (pintype "passive"))
      (node (ref "SWITCH_M7") (pin "2") (pinfunction "2_2") (pintype "passive"))
      (node (ref "SWR_7") (pin "2") (pinfunction "2_2") (pintype "passive"))
      (node (ref "U2") (pin "14") (pinfunction "I/O[9]_14") (pintype "bidirectional"))
    )
    (net (code "35") (name "9_SX3") (class "Default")
      (node (ref "RN1") (pin "4") (pinfunction "1_4") (pintype "passive"))
      (node (ref "SW1") (pin "17") (pinfunction "17_17") (pintype "passive"))
      (node (ref "U4") (pin "14") (pinfunction "I/O[9]_14") (pintype "bidirectional"))
    )
    (net (code "36") (name "10_SX1") (class "Default")
      (node (ref "M_01") (pin "6") (pinfunction "6_6") (pintype "passive"))
      (node (ref "U1") (pin "15") (pinfunction "I/O[10]_15") (pintype "bidirectional"))
    )
    (net (code "37") (name "10_SX2") (class "Default")
      (node (ref "M_05") (pin "6") (pinfunction "6_6") (pintype "passive"))
      (node (ref "U2") (pin "15") (pinfunction "I/O[10]_15") (pintype "bidirectional"))
    )
    (net (code "38") (name "10_SX3") (class "Default")
      (node (ref "RN3") (pin "1") (pinfunction "1_1") (pintype "passive"))
      (node (ref "SW1") (pin "16") (pinfunction "16_16") (pintype "passive"))
      (node (ref "U4") (pin "15") (pinfunction "I/O[10]_15") (pintype "bidirectional"))
    )
    (net (code "39") (name "11_SX1") (class "Default")
      (node (ref "M_01") (pin "5") (pinfunction "5_5") (pintype "passive"))
      (node (ref "U1") (pin "16") (pinfunction "I/O[11]_16") (pintype "bidirectional"))
    )
    (net (code "40") (name "11_SX2") (class "Default")
      (node (ref "M_05") (pin "5") (pinfunction "5_5") (pintype "passive"))
      (node (ref "U2") (pin "16") (pinfunction "I/O[11]_16") (pintype "bidirectional"))
    )
    (net (code "41") (name "11_SX3") (class "Default")
      (node (ref "RN3") (pin "2") (pinfunction "1_2") (pintype "passive"))
      (node (ref "SW1") (pin "15") (pinfunction "15_15") (pintype "passive"))
      (node (ref "U4") (pin "16") (pinfunction "I/O[11]_16") (pintype "bidirectional"))
    )
    (net (code "42") (name "12_SX1") (class "Default")
      (node (ref "M_01") (pin "4") (pinfunction "4_4") (pintype "passive"))
      (node (ref "U1") (pin "19") (pinfunction "I/O[12]_19") (pintype "bidirectional"))
    )
    (net (code "43") (name "12_SX2") (class "Default")
      (node (ref "M_05") (pin "4") (pinfunction "4_4") (pintype "passive"))
      (node (ref "U2") (pin "19") (pinfunction "I/O[12]_19") (pintype "bidirectional"))
    )
    (net (code "44") (name "12_SX3") (class "Default")
      (node (ref "RN3") (pin "3") (pinfunction "1_3") (pintype "passive"))
      (node (ref "SW1") (pin "14") (pinfunction "14_14") (pintype "passive"))
      (node (ref "U4") (pin "19") (pinfunction "I/O[12]_19") (pintype "bidirectional"))
    )
    (net (code "45") (name "13_SX1") (class "Default")
      (node (ref "M_03") (pin "6") (pinfunction "6_6") (pintype "passive"))
      (node (ref "U1") (pin "20") (pinfunction "I/O[13]_20") (pintype "bidirectional"))
    )
    (net (code "46") (name "13_SX2") (class "Default")
      (node (ref "M_07") (pin "6") (pinfunction "6_6") (pintype "passive"))
      (node (ref "U2") (pin "20") (pinfunction "I/O[13]_20") (pintype "bidirectional"))
    )
    (net (code "47") (name "13_SX3") (class "Default")
      (node (ref "RN3") (pin "4") (pinfunction "1_4") (pintype "passive"))
      (node (ref "SW1") (pin "13") (pinfunction "13_13") (pintype "passive"))
      (node (ref "U4") (pin "20") (pinfunction "I/O[13]_20") (pintype "bidirectional"))
    )
    (net (code "48") (name "14_SX1") (class "Default")
      (node (ref "M_03") (pin "5") (pinfunction "5_5") (pintype "passive"))
      (node (ref "U1") (pin "21") (pinfunction "I/O[14]_21") (pintype "bidirectional"))
    )
    (net (code "49") (name "14_SX2") (class "Default")
      (node (ref "M_07") (pin "5") (pinfunction "5_5") (pintype "passive"))
      (node (ref "U2") (pin "21") (pinfunction "I/O[14]_21") (pintype "bidirectional"))
    )
    (net (code "50") (name "14_SX3") (class "Default")
      (node (ref "RN2") (pin "1") (pinfunction "1_1") (pintype "passive"))
      (node (ref "SW1") (pin "12") (pinfunction "12_12") (pintype "passive"))
      (node (ref "U4") (pin "21") (pinfunction "I/O[14]_21") (pintype "bidirectional"))
    )
    (net (code "51") (name "15_SX1") (class "Default")
      (node (ref "M_03") (pin "4") (pinfunction "4_4") (pintype "passive"))
      (node (ref "U1") (pin "22") (pinfunction "I/O[15]_22") (pintype "bidirectional"))
    )
    (net (code "52") (name "15_SX2") (class "Default")
      (node (ref "M_07") (pin "4") (pinfunction "4_4") (pintype "passive"))
      (node (ref "U2") (pin "22") (pinfunction "I/O[15]_22") (pintype "bidirectional"))
    )
    (net (code "53") (name "15_SX3") (class "Default")
      (node (ref "RN2") (pin "2") (pinfunction "1_2") (pintype "passive"))
      (node (ref "SW1") (pin "11") (pinfunction "11_11") (pintype "passive"))
      (node (ref "U4") (pin "22") (pinfunction "I/O[15]_22") (pintype "bidirectional"))
    )
    (net (code "54") (name "ADDR0_SX1") (class "Default")
      (node (ref "JP8") (pin "1") (pinfunction "1_1") (pintype "passive"))
      (node (ref "U1") (pin "26") (pinfunction "ADDR0_26") (pintype "bidirectional"))
    )
    (net (code "55") (name "ADDR0_SX2") (class "Default")
      (node (ref "JP7") (pin "1") (pinfunction "1_1") (pintype "passive"))
      (node (ref "U2") (pin "26") (pinfunction "ADDR0_26") (pintype "bidirectional"))
    )
    (net (code "56") (name "ADDR0_SX3") (class "Default")
      (node (ref "JP11") (pin "1") (pinfunction "1_1") (pintype "passive"))
      (node (ref "U4") (pin "26") (pinfunction "ADDR0_26") (pintype "bidirectional"))
    )
    (net (code "57") (name "ADDR1_SX1") (class "Default")
      (node (ref "JP9") (pin "1") (pinfunction "1_1") (pintype "passive"))
      (node (ref "U1") (pin "10") (pinfunction "ADDR1_10") (pintype "bidirectional"))
    )
    (net (code "58") (name "ADDR1_SX2") (class "Default")
      (node (ref "JP6") (pin "1") (pinfunction "1_1") (pintype "passive"))
      (node (ref "U2") (pin "10") (pinfunction "ADDR1_10") (pintype "bidirectional"))
    )
    (net (code "59") (name "ADDR1_SX3") (class "Default")
      (node (ref "JP10") (pin "1") (pinfunction "1_1") (pintype "passive"))
      (node (ref "U4") (pin "10") (pinfunction "ADDR1_10") (pintype "bidirectional"))
    )
    (net (code "60") (name "GND_MCU") (class "Default")
      (node (ref "C1") (pin "2") (pinfunction "2_2") (pintype "passive"))
      (node (ref "C2") (pin "2") (pinfunction "2_2") (pintype "passive"))
      (node (ref "C3") (pin "2") (pinfunction "2_2") (pintype "passive"))
      (node (ref "C4") (pin "2") (pinfunction "2_2") (pintype "passive"))
      (node (ref "C5") (pin "2") (pinfunction "2_2") (pintype "passive"))
      (node (ref "C6") (pin "2") (pinfunction "2_2") (pintype "passive"))
      (node (ref "C7") (pin "2") (pinfunction "2_2") (pintype "passive"))
      (node (ref "C8") (pin "2") (pinfunction "2_2") (pintype "passive"))
      (node (ref "C9") (pin "2") (pinfunction "2_2") (pintype "passive"))
      (node (ref "J3") (pin "18") (pinfunction "18_18") (pintype "passive"))
      (node (ref "J3") (pin "20") (pinfunction "20_20") (pintype "passive"))
      (node (ref "JP7") (pin "2") (pinfunction "2_2") (pintype "passive"))
      (node (ref "JP9") (pin "2") (pinfunction "2_2") (pintype "passive"))
      (node (ref "M_01") (pin "1") (pinfunction "1_1") (pintype "passive"))
      (node (ref "M_02") (pin "1") (pinfunction "1_1") (pintype "passive"))
      (node (ref "M_03") (pin "1") (pinfunction "1_1") (pintype "passive"))
      (node (ref "M_04") (pin "1") (pinfunction "1_1") (pintype "passive"))
      (node (ref "M_05") (pin "1") (pinfunction "1_1") (pintype "passive"))
      (node (ref "M_06") (pin "1") (pinfunction "1_1") (pintype "passive"))
      (node (ref "M_07") (pin "1") (pinfunction "1_1") (pintype "passive"))
      (node (ref "M_08") (pin "1") (pinfunction "1_1") (pintype "passive"))
      (node (ref "POWE_3.3") (pin "2") (pinfunction "C_2") (pintype "passive"))
      (node (ref "R1") (pin "1") (pinfunction "1_1") (pintype "passive"))
      (node (ref "R2") (pin "1") (pinfunction "1_1") (pintype "passive"))
      (node (ref "R3") (pin "1") (pinfunction "1_1") (pintype "passive"))
      (node (ref "R4") (pin "1") (pinfunction "1_1") (pintype "passive"))
      (node (ref "R5") (pin "1") (pinfunction "1_1") (pintype "passive"))
      (node (ref "R6") (pin "1") (pinfunction "1_1") (pintype "passive"))
      (node (ref "R7") (pin "1") (pinfunction "1_1") (pintype "passive"))
      (node (ref "R8") (pin "1") (pinfunction "1_1") (pintype "passive"))
      (node (ref "RN2") (pin "3") (pinfunction "1_3") (pintype "passive"))
      (node (ref "STATUS_LED") (pin "2") (pinfunction "C_2") (pintype "passive"))
      (node (ref "SW1") (pin "1") (pinfunction "1_1") (pintype "passive"))
      (node (ref "SW1") (pin "10") (pinfunction "10_10") (pintype "passive"))
      (node (ref "SW1") (pin "2") (pinfunction "2_2") (pintype "passive"))
      (node (ref "SW1") (pin "3") (pinfunction "3_3") (pintype "passive"))
      (node (ref "SW1") (pin "4") (pinfunction "4_4") (pintype "passive"))
      (node (ref "SW1") (pin "5") (pinfunction "5_5") (pintype "passive"))
      (node (ref "SW1") (pin "6") (pinfunction "6_6") (pintype "passive"))
      (node (ref "SW1") (pin "7") (pinfunction "7_7") (pintype "passive"))
      (node (ref "SW1") (pin "8") (pinfunction "8_8") (pintype "passive"))
      (node (ref "SW1") (pin "9") (pinfunction "9_9") (pintype "passive"))
      (node (ref "SWR_1") (pin "1") (pinfunction "1_1") (pintype "passive"))
      (node (ref "SWR_2") (pin "1") (pinfunction "1_1") (pintype "passive"))
      (node (ref "SWR_3") (pin "1") (pinfunction "1_1") (pintype "passive"))
      (node (ref "SWR_4") (pin "1") (pinfunction "1_1") (pintype "passive"))
      (node (ref "SWR_5") (pin "1") (pinfunction "1_1") (pintype "passive"))
      (node (ref "SWR_6") (pin "1") (pinfunction "1_1") (pintype "passive"))
      (node (ref "SWR_7") (pin "1") (pinfunction "1_1") (pintype "passive"))
      (node (ref "SWR_8") (pin "1") (pinfunction "1_1") (pintype "passive"))
      (node (ref "U1") (pin "17") (pinfunction "GND_17") (pintype "bidirectional"))
      (node (ref "U1") (pin "29") (pinfunction "GND_29") (pintype "bidirectional"))
      (node (ref "U1") (pin "3") (pinfunction "GND_3") (pintype "bidirectional"))
      (node (ref "U2") (pin "17") (pinfunction "GND_17") (pintype "bidirectional"))
      (node (ref "U2") (pin "29") (pinfunction "GND_29") (pintype "bidirectional"))
      (node (ref "U2") (pin "3") (pinfunction "GND_3") (pintype "bidirectional"))
      (node (ref "U4") (pin "17") (pinfunction "GND_17") (pintype "bidirectional"))
      (node (ref "U4") (pin "29") (pinfunction "GND_29") (pintype "bidirectional"))
      (node (ref "U4") (pin "3") (pinfunction "GND_3") (pintype "bidirectional"))
    )
    (net (code "61") (name "INT_01") (class "Default")
      (node (ref "J3") (pin "6") (pinfunction "6_6") (pintype "passive"))
      (node (ref "R12") (pin "1") (pinfunction "1_1") (pintype "passive"))
      (node (ref "U1") (pin "9") (pinfunction "~{INT}_9") (pintype "bidirectional"))
    )
    (net (code "62") (name "INT_02") (class "Default")
      (node (ref "J3") (pin "8") (pinfunction "8_8") (pintype "passive"))
      (node (ref "R19") (pin "1") (pinfunction "1_1") (pintype "passive"))
      (node (ref "U2") (pin "9") (pinfunction "~{INT}_9") (pintype "bidirectional"))
    )
    (net (code "63") (name "NEOPIXEL_01") (class "Default")
      (node (ref "J3") (pin "1") (pinfunction "1_1") (pintype "passive"))
      (node (ref "M_01") (pin "3") (pinfunction "3_3") (pintype "passive"))
    )
    (net (code "64") (name "NEOPIXEL_02") (class "Default")
      (node (ref "J3") (pin "3") (pinfunction "3_3") (pintype "passive"))
      (node (ref "M_02") (pin "3") (pinfunction "3_3") (pintype "passive"))
    )
    (net (code "65") (name "NEOPIXEL_03") (class "Default")
      (node (ref "J3") (pin "5") (pinfunction "5_5") (pintype "passive"))
      (node (ref "M_03") (pin "3") (pinfunction "3_3") (pintype "passive"))
    )
    (net (code "66") (name "NEOPIXEL_04") (class "Default")
      (node (ref "J3") (pin "7") (pinfunction "7_7") (pintype "passive"))
      (node (ref "M_04") (pin "3") (pinfunction "3_3") (pintype "passive"))
    )
    (net (code "67") (name "NEOPIXEL_05") (class "Default")
      (node (ref "J3") (pin "9") (pinfunction "9_9") (pintype "passive"))
      (node (ref "M_05") (pin "3") (pinfunction "3_3") (pintype "passive"))
    )
    (net (code "68") (name "NEOPIXEL_06") (class "Default")
      (node (ref "J3") (pin "11") (pinfunction "11_11") (pintype "passive"))
      (node (ref "M_06") (pin "3") (pinfunction "3_3") (pintype "passive"))
    )
    (net (code "69") (name "NEOPIXEL_07") (class "Default")
      (node (ref "J3") (pin "13") (pinfunction "13_13") (pintype "passive"))
      (node (ref "M_07") (pin "3") (pinfunction "3_3") (pintype "passive"))
    )
    (net (code "70") (name "NEOPIXEL_08") (class "Default")
      (node (ref "J3") (pin "15") (pinfunction "15_15") (pintype "passive"))
      (node (ref "M_08") (pin "3") (pinfunction "3_3") (pintype "passive"))
    )
    (net (code "71") (name "Net-(JP6-Pad2)") (class "Default")
      (node (ref "JP6") (pin "2") (pinfunction "2_2") (pintype "passive"))
      (node (ref "R21") (pin "1") (pinfunction "1_1") (pintype "passive"))
    )
    (net (code "72") (name "Net-(JP8-Pad2)") (class "Default")
      (node (ref "JP8") (pin "2") (pinfunction "2_2") (pintype "passive"))
      (node (ref "R13") (pin "1") (pinfunction "1_1") (pintype "passive"))
    )
    (net (code "73") (name "Net-(JP10-Pad2)") (class "Default")
      (node (ref "JP10") (pin "2") (pinfunction "2_2") (pintype "passive"))
      (node (ref "R25") (pin "1") (pinfunction "1_1") (pintype "passive"))
    )
    (net (code "74") (name "Net-(JP11-Pad2)") (class "Default")
      (node (ref "JP11") (pin "2") (pinfunction "2_2") (pintype "passive"))
      (node (ref "R26") (pin "1") (pinfunction "1_1") (pintype "passive"))
    )
    (net (code "75") (name "Net-(POWE_3.3-A)") (class "Default")
      (node (ref "POWE_3.3") (pin "1") (pinfunction "A_1") (pintype "passive"))
      (node (ref "R27") (pin "1") (pinfunction "1_1") (pintype "passive"))
    )
    (net (code "76") (name "Net-(STATUS_LED-A)") (class "Default")
      (node (ref "R28") (pin "1") (pinfunction "1_1") (pintype "passive"))
      (node (ref "STATUS_LED") (pin "1") (pinfunction "A_1") (pintype "passive"))
    )
    (net (code "77") (name "OSCIO_SX1") (class "Default")
      (node (ref "U1") (pin "11") (pinfunction "OSCIO_11") (pintype "bidirectional"))
    )
    (net (code "78") (name "OSCIO_SX2") (class "Default")
      (node (ref "U2") (pin "11") (pinfunction "OSCIO_11") (pintype "bidirectional"))
    )
    (net (code "79") (name "OSCIO_SX3") (class "Default")
      (node (ref "U4") (pin "11") (pinfunction "OSCIO_11") (pintype "bidirectional"))
    )
    (net (code "80") (name "RESET") (class "Default")
      (node (ref "J3") (pin "10") (pinfunction "10_10") (pintype "passive"))
      (node (ref "JP1") (pin "2") (pinfunction "2_2") (pintype "passive"))
      (node (ref "JP1") (pin "3") (pinfunction "3_3") (pintype "passive"))
      (node (ref "RN2") (pin "6") (pinfunction "2_6") (pintype "passive"))
      (node (ref "S2") (pin "3") (pinfunction "3_3") (pintype "passive"))
      (node (ref "S2") (pin "4") (pinfunction "4_4") (pintype "passive"))
    )
    (net (code "81") (name "SCL_00") (class "Default")
      (node (ref "J3") (pin "4") (pinfunction "4_4") (pintype "passive"))
      (node (ref "R11") (pin "1") (pinfunction "1_1") (pintype "passive"))
      (node (ref "R18") (pin "1") (pinfunction "1_1") (pintype "passive"))
      (node (ref "R23") (pin "1") (pinfunction "1_1") (pintype "passive"))
      (node (ref "U1") (pin "25") (pinfunction "SCL_25") (pintype "bidirectional"))
      (node (ref "U2") (pin "25") (pinfunction "SCL_25") (pintype "bidirectional"))
      (node (ref "U4") (pin "25") (pinfunction "SCL_25") (pintype "bidirectional"))
    )
    (net (code "82") (name "SDA_00") (class "Default")
      (node (ref "J3") (pin "2") (pinfunction "2_2") (pintype "passive"))
      (node (ref "R10") (pin "1") (pinfunction "1_1") (pintype "passive"))
      (node (ref "R17") (pin "1") (pinfunction "1_1") (pintype "passive"))
      (node (ref "R20") (pin "1") (pinfunction "1_1") (pintype "passive"))
      (node (ref "U1") (pin "24") (pinfunction "SDA_24") (pintype "bidirectional"))
      (node (ref "U2") (pin "24") (pinfunction "SDA_24") (pintype "bidirectional"))
      (node (ref "U4") (pin "24") (pinfunction "SDA_24") (pintype "bidirectional"))
    )
    (net (code "83") (name "VCC_5V") (class "Default")
      (node (ref "M_01") (pin "2") (pinfunction "2_2") (pintype "passive"))
      (node (ref "M_02") (pin "2") (pinfunction "2_2") (pintype "passive"))
      (node (ref "M_03") (pin "2") (pinfunction "2_2") (pintype "passive"))
      (node (ref "M_04") (pin "2") (pinfunction "2_2") (pintype "passive"))
      (node (ref "M_05") (pin "2") (pinfunction "2_2") (pintype "passive"))
      (node (ref "M_06") (pin "2") (pinfunction "2_2") (pintype "passive"))
      (node (ref "M_07") (pin "2") (pinfunction "2_2") (pintype "passive"))
      (node (ref "M_08") (pin "2") (pinfunction "2_2") (pintype "passive"))
      (node (ref "S1") (pin "4") (pinfunction "4_4") (pintype "passive"))
      (node (ref "S1") (pin "8") (pinfunction "8_8") (pintype "passive"))
    )
    (net (code "84") (name "VCC_5V_IN") (class "Default")
      (node (ref "J3") (pin "17") (pinfunction "17_17") (pintype "passive"))
      (node (ref "S1") (pin "3") (pinfunction "3_3") (pintype "passive"))
      (node (ref "S1") (pin "7") (pinfunction "7_7") (pintype "passive"))
    )
    (net (code "85") (name "unconnected-(RN2D-1-Pad4)") (class "Default")
      (node (ref "RN2") (pin "4") (pinfunction "1_4") (pintype "passive"))
    )
    (net (code "86") (name "unconnected-(RN2D-2-Pad5)") (class "Default")
      (node (ref "RN2") (pin "5") (pinfunction "2_5") (pintype "passive"))
    )
    (net (code "87") (name "unconnected-(S1-Pad1)") (class "Default")
      (node (ref "S1") (pin "1") (pinfunction "1_1") (pintype "passive"))
    )
    (net (code "88") (name "unconnected-(S1-Pad2)") (class "Default")
      (node (ref "S1") (pin "2") (pinfunction "2_2") (pintype "passive"))
    )
    (net (code "89") (name "unconnected-(S1-Pad5)") (class "Default")
      (node (ref "S1") (pin "5") (pinfunction "5_5") (pintype "passive"))
    )
    (net (code "90") (name "unconnected-(S1-Pad6)") (class "Default")
      (node (ref "S1") (pin "6") (pinfunction "6_6") (pintype "passive"))
    )
    (net (code "91") (name "unconnected-(SWB_1-Pad2)") (class "Default")
      (node (ref "SWB_1") (pin "2") (pinfunction "2_2") (pintype "passive"))
    )
    (net (code "92") (name "unconnected-(SWB_1-Pad4)") (class "Default")
      (node (ref "SWB_1") (pin "4") (pinfunction "4_4") (pintype "passive"))
    )
    (net (code "93") (name "unconnected-(SWB_2-Pad2)") (class "Default")
      (node (ref "SWB_2") (pin "2") (pinfunction "2_2") (pintype "passive"))
    )
    (net (code "94") (name "unconnected-(SWB_2-Pad4)") (class "Default")
      (node (ref "SWB_2") (pin "4") (pinfunction "4_4") (pintype "passive"))
    )
    (net (code "95") (name "unconnected-(SWB_3-Pad2)") (class "Default")
      (node (ref "SWB_3") (pin "2") (pinfunction "2_2") (pintype "passive"))
    )
    (net (code "96") (name "unconnected-(SWB_3-Pad4)") (class "Default")
      (node (ref "SWB_3") (pin "4") (pinfunction "4_4") (pintype "passive"))
    )
    (net (code "97") (name "unconnected-(SWB_4-Pad2)") (class "Default")
      (node (ref "SWB_4") (pin "2") (pinfunction "2_2") (pintype "passive"))
    )
    (net (code "98") (name "unconnected-(SWB_4-Pad4)") (class "Default")
      (node (ref "SWB_4") (pin "4") (pinfunction "4_4") (pintype "passive"))
    )
    (net (code "99") (name "unconnected-(SWB_5-Pad2)") (class "Default")
      (node (ref "SWB_5") (pin "2") (pinfunction "2_2") (pintype "passive"))
    )
    (net (code "100") (name "unconnected-(SWB_5-Pad4)") (class "Default")
      (node (ref "SWB_5") (pin "4") (pinfunction "4_4") (pintype "passive"))
    )
    (net (code "101") (name "unconnected-(SWB_6-Pad2)") (class "Default")
      (node (ref "SWB_6") (pin "2") (pinfunction "2_2") (pintype "passive"))
    )
    (net (code "102") (name "unconnected-(SWB_6-Pad4)") (class "Default")
      (node (ref "SWB_6") (pin "4") (pinfunction "4_4") (pintype "passive"))
    )
    (net (code "103") (name "unconnected-(SWB_7-Pad2)") (class "Default")
      (node (ref "SWB_7") (pin "2") (pinfunction "2_2") (pintype "passive"))
    )
    (net (code "104") (name "unconnected-(SWB_7-Pad4)") (class "Default")
      (node (ref "SWB_7") (pin "4") (pinfunction "4_4") (pintype "passive"))
    )
    (net (code "105") (name "unconnected-(SWB_8-Pad2)") (class "Default")
      (node (ref "SWB_8") (pin "2") (pinfunction "2_2") (pintype "passive"))
    )
    (net (code "106") (name "unconnected-(SWB_8-Pad4)") (class "Default")
      (node (ref "SWB_8") (pin "4") (pinfunction "4_4") (pintype "passive"))
    )
  )
)
